# badi.net
KiCad netlist of a schematic drawn in EAGLE
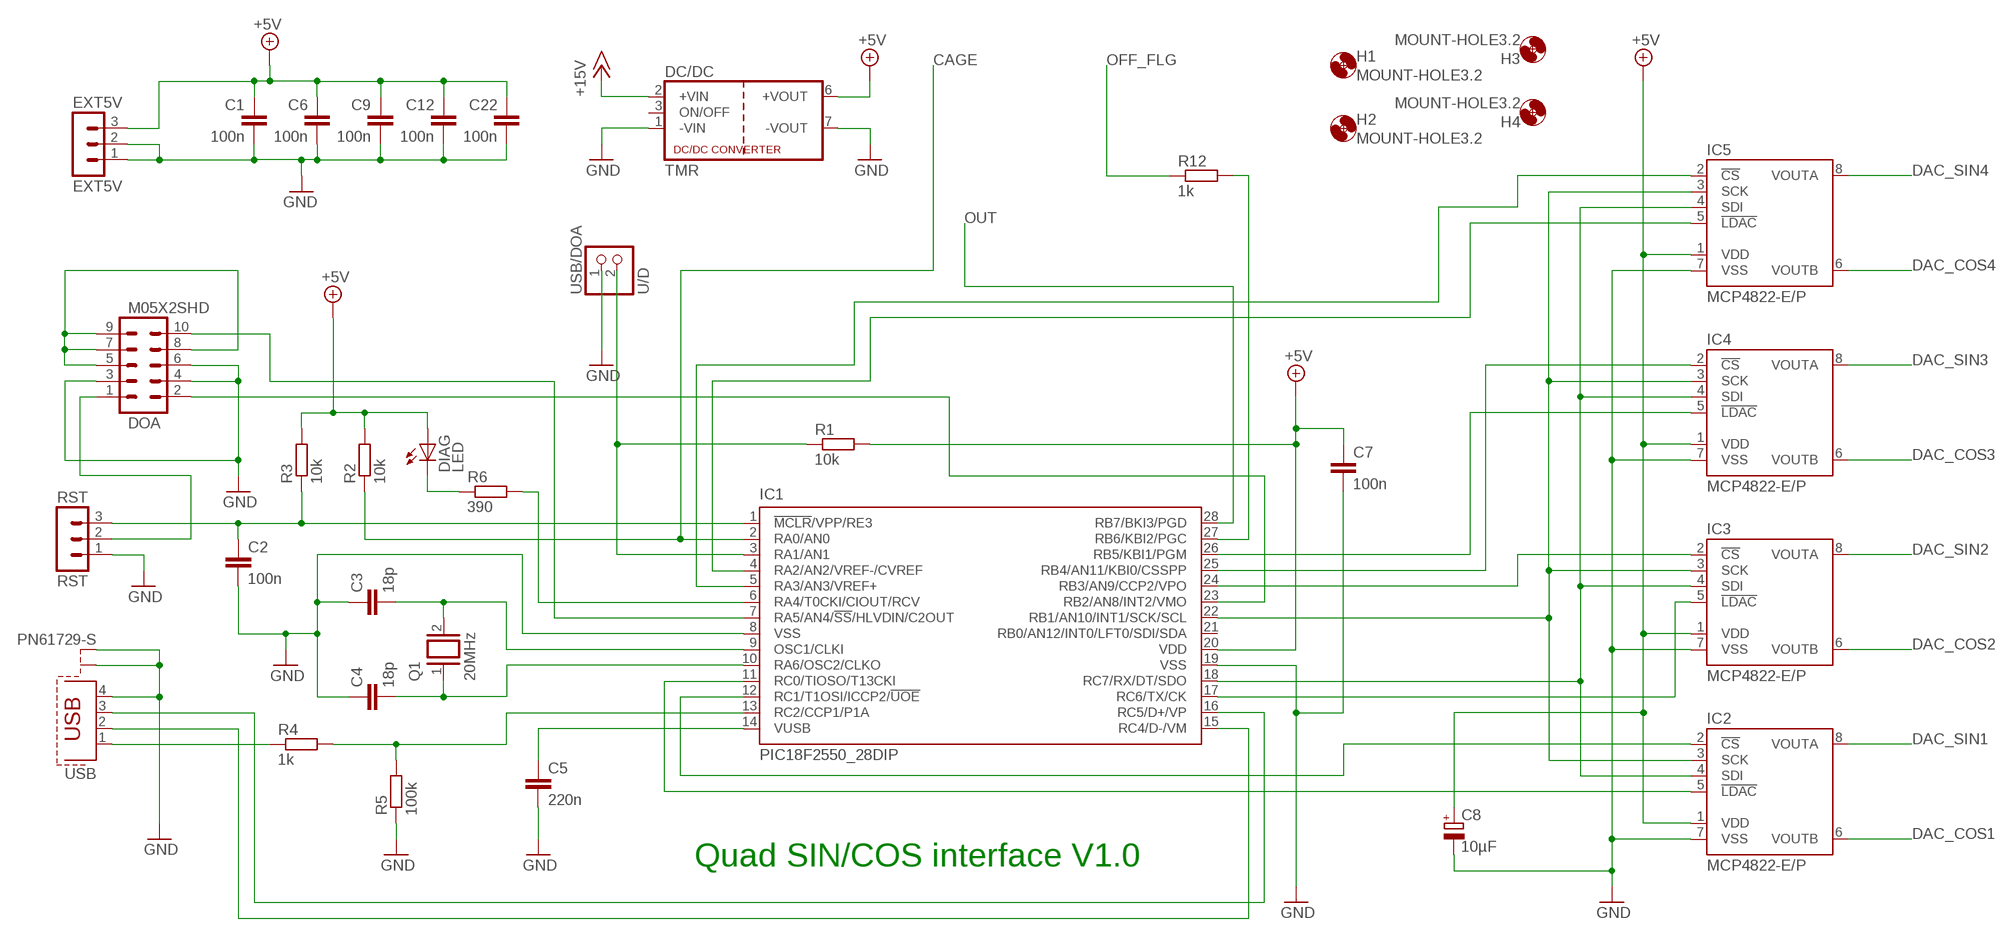
[diagram p0: schematic, sheet 1]
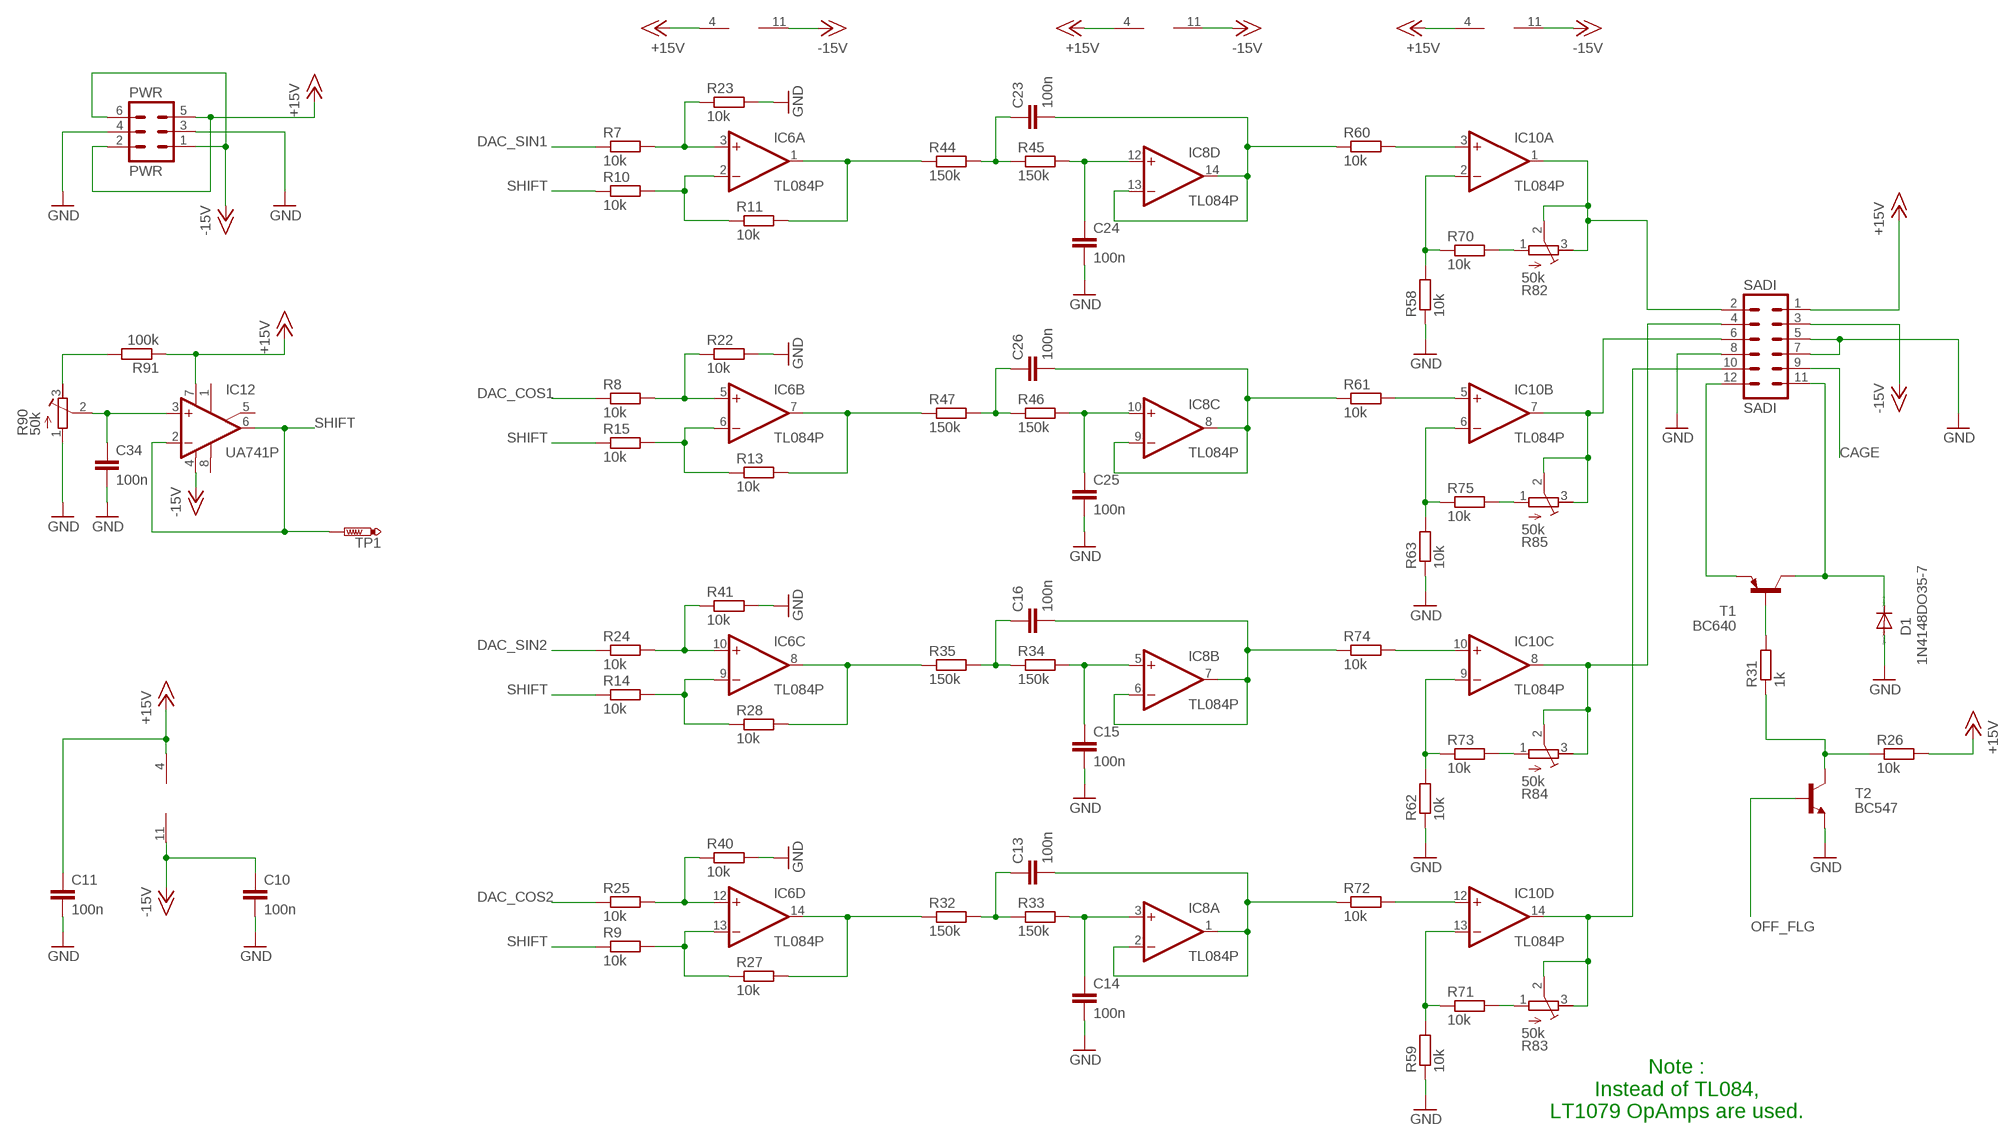
[diagram p1: schematic, sheet 2, part 1 of 2]
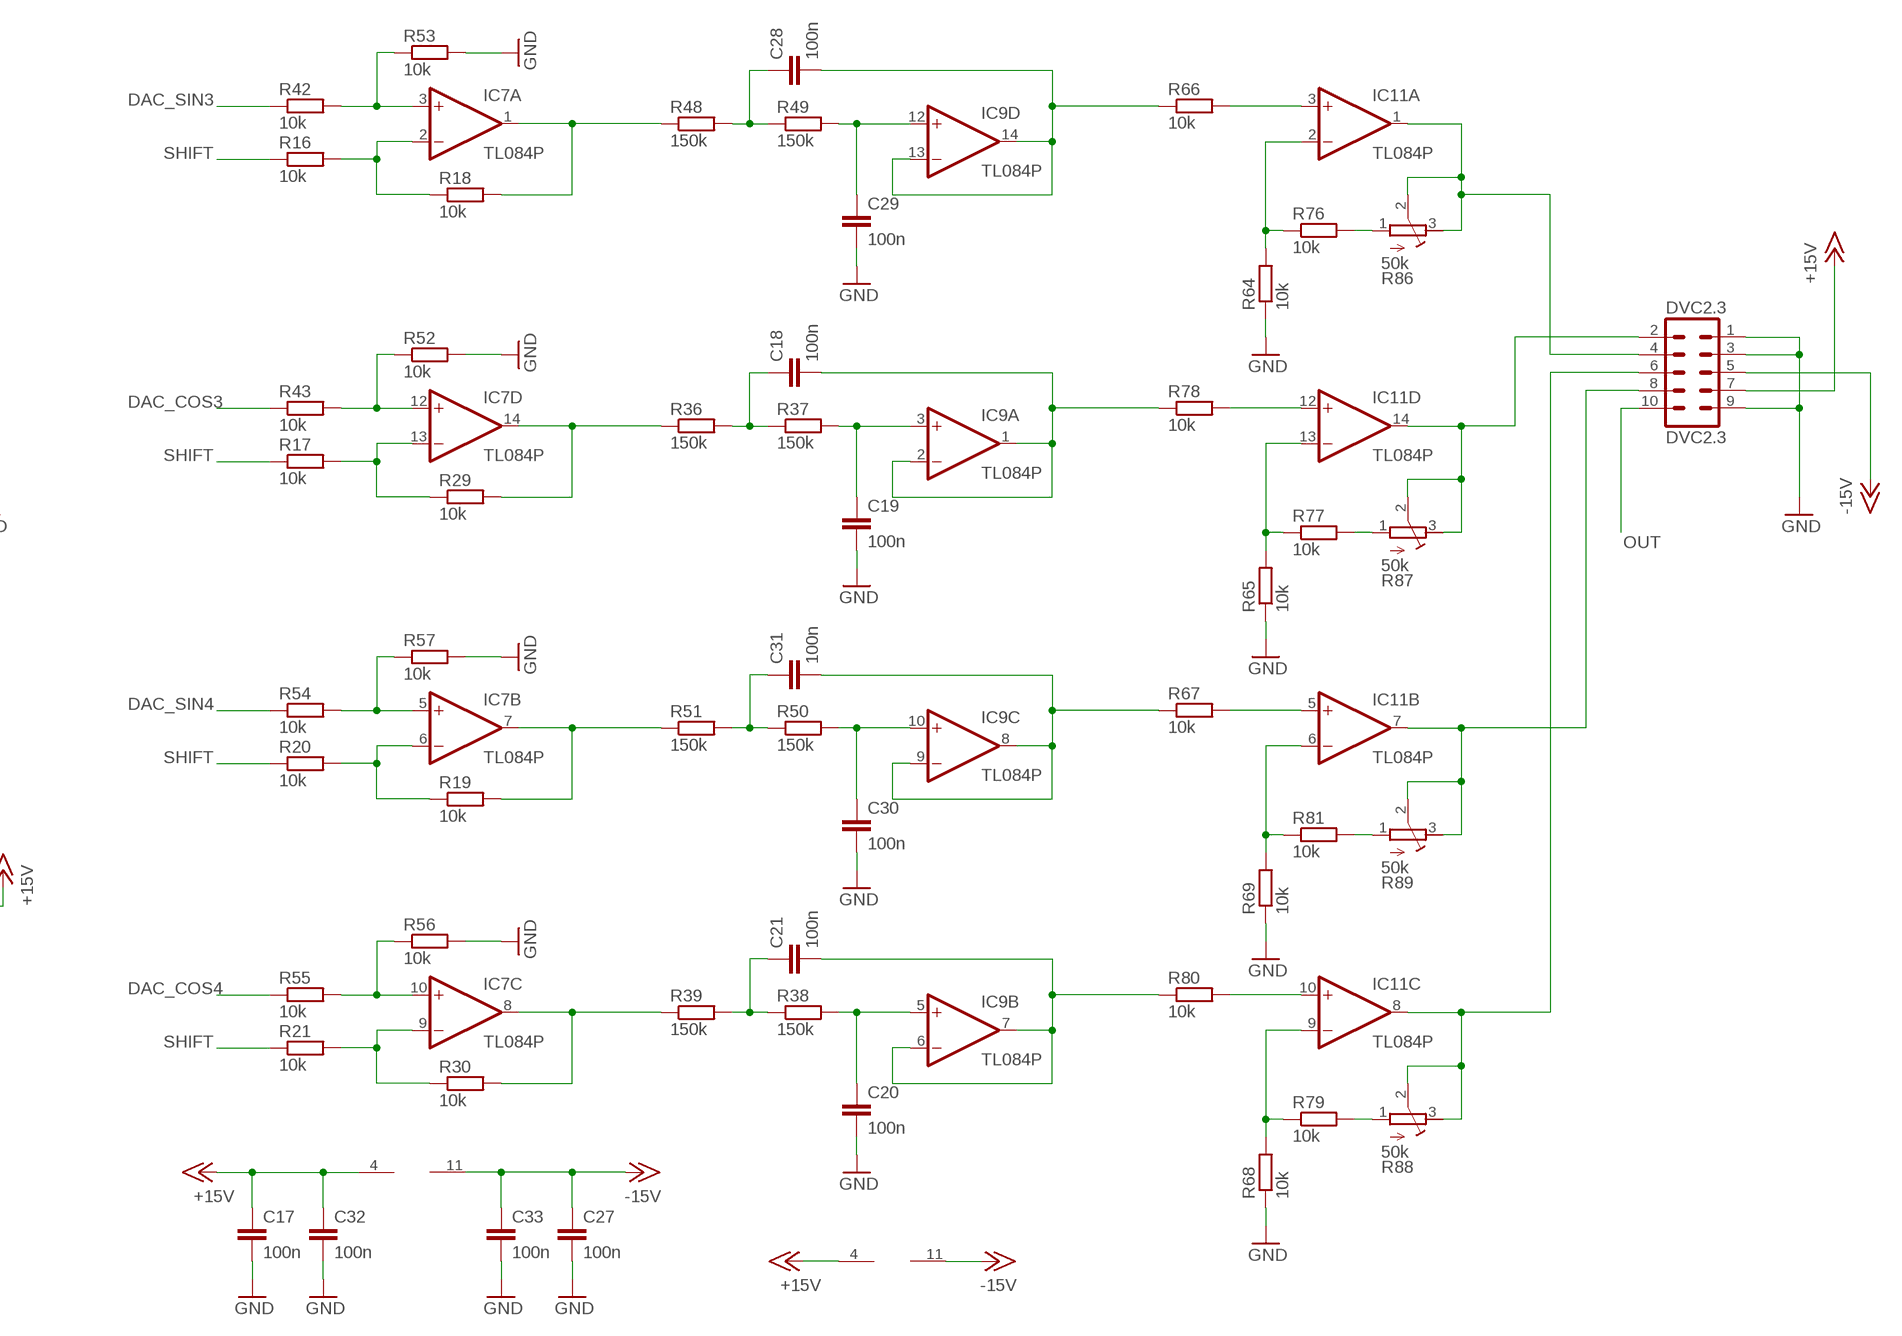
[diagram p2: schematic, sheet 2, part 2 of 2]

(export (version "E")
  (design (tool "Eeschema 10.0.6"))
  (components
    (comp (ref "C1")
      (value "100n")
      (footprint "eagle-import:C025-025X050")
      (libsource (lib "eagle-import") (part "C-EU025-025X050"))
    )
    (comp (ref "C2")
      (value "100n")
      (footprint "eagle-import:C025-025X050")
      (libsource (lib "eagle-import") (part "C-EU025-025X050"))
    )
    (comp (ref "C3")
      (value "18p")
      (footprint "eagle-import:C025-025X050")
      (libsource (lib "eagle-import") (part "C-EU025-025X050"))
    )
    (comp (ref "C4")
      (value "18p")
      (footprint "eagle-import:C025-025X050")
      (libsource (lib "eagle-import") (part "C-EU025-025X050"))
    )
    (comp (ref "C5")
      (value "220n")
      (footprint "eagle-import:C5B3")
      (libsource (lib "eagle-import") (part "C5/3"))
    )
    (comp (ref "C6")
      (value "100n")
      (footprint "eagle-import:C025-025X050")
      (libsource (lib "eagle-import") (part "C-EU025-025X050"))
    )
    (comp (ref "C7")
      (value "100n")
      (footprint "eagle-import:C025-025X050")
      (libsource (lib "eagle-import") (part "C-EU025-025X050"))
    )
    (comp (ref "C8")
      (value "10µF")
      (footprint "eagle-import:E2,5-5")
      (libsource (lib "eagle-import") (part "CPOL-EUE2.5-5"))
    )
    (comp (ref "C9")
      (value "100n")
      (footprint "eagle-import:C025-025X050")
      (libsource (lib "eagle-import") (part "C-EU025-025X050"))
    )
    (comp (ref "C12")
      (value "100n")
      (footprint "eagle-import:C025-025X050")
      (libsource (lib "eagle-import") (part "C-EU025-025X050"))
    )
    (comp (ref "C22")
      (value "100n")
      (footprint "eagle-import:C025-025X050")
      (libsource (lib "eagle-import") (part "C-EU025-025X050"))
    )
    (comp (ref "DC/DC")
      (value "TMR")
      (footprint "eagle-import:TRACO_SIP-8")
      (libsource (lib "eagle-import") (part "TMR"))
    )
    (comp (ref "DIAG")
      (value "LED")
      (footprint "eagle-import:LED3MM")
      (libsource (lib "eagle-import") (part "LED3MM"))
    )
    (comp (ref "DOA")
      (value "M05X2SHD")
      (footprint "eagle-import:2X5-SHROUDED")
      (libsource (lib "eagle-import") (part "M05X2SHD"))
    )
    (comp (ref "EXT5V")
      (value "EXT5V")
      (footprint "eagle-import:MA03-1")
      (libsource (lib "eagle-import") (part "MA03-1"))
    )
    (comp (ref "H1")
      (value "MOUNT-HOLE3.2")
      (footprint "eagle-import:3,2")
      (libsource (lib "eagle-import") (part "MOUNT-HOLE3.2"))
    )
    (comp (ref "H2")
      (value "MOUNT-HOLE3.2")
      (footprint "eagle-import:3,2")
      (libsource (lib "eagle-import") (part "MOUNT-HOLE3.2"))
    )
    (comp (ref "H3")
      (value "MOUNT-HOLE3.2")
      (footprint "eagle-import:3,2")
      (libsource (lib "eagle-import") (part "MOUNT-HOLE3.2"))
    )
    (comp (ref "H4")
      (value "MOUNT-HOLE3.2")
      (footprint "eagle-import:3,2")
      (libsource (lib "eagle-import") (part "MOUNT-HOLE3.2"))
    )
    (comp (ref "IC1")
      (value "PIC18F2550_28DIP")
      (footprint "eagle-import:DIL28-3")
      (fields (field (name "MF") "MICROCHIP") (field (name "MPN") "PIC18F2550-I/SP"))
      (libsource (lib "eagle-import") (part "PIC18F2_28DIP550"))
    )
    (comp (ref "IC2")
      (value "MCP4822-E/P")
      (footprint "eagle-import:DIL08")
      (libsource (lib "eagle-import") (part "MCP4822-E/P"))
    )
    (comp (ref "IC3")
      (value "MCP4822-E/P")
      (footprint "eagle-import:DIL08")
      (libsource (lib "eagle-import") (part "MCP4822-E/P"))
    )
    (comp (ref "IC4")
      (value "MCP4822-E/P")
      (footprint "eagle-import:DIL08")
      (libsource (lib "eagle-import") (part "MCP4822-E/P"))
    )
    (comp (ref "IC5")
      (value "MCP4822-E/P")
      (footprint "eagle-import:DIL08")
      (libsource (lib "eagle-import") (part "MCP4822-E/P"))
    )
    (comp (ref "Q1")
      (value "20MHz")
      (footprint "eagle-import:QS")
      (libsource (lib "eagle-import") (part "XTAL/S"))
    )
    (comp (ref "R1")
      (value "10k")
      (footprint "eagle-import:0204_7")
      (libsource (lib "eagle-import") (part "R-EU_0204/7"))
    )
    (comp (ref "R2")
      (value "10k")
      (footprint "eagle-import:0204_7")
      (libsource (lib "eagle-import") (part "R-EU_0204/7"))
    )
    (comp (ref "R3")
      (value "10k")
      (footprint "eagle-import:0204_7")
      (libsource (lib "eagle-import") (part "R-EU_0204/7"))
    )
    (comp (ref "R4")
      (value "1k")
      (footprint "eagle-import:0204_7")
      (libsource (lib "eagle-import") (part "R-EU_0204/7"))
    )
    (comp (ref "R5")
      (value "100k")
      (footprint "eagle-import:0204_7")
      (libsource (lib "eagle-import") (part "R-EU_0204/7"))
    )
    (comp (ref "R6")
      (value "390")
      (footprint "eagle-import:0204_7")
      (libsource (lib "eagle-import") (part "R-EU_0204/7"))
    )
    (comp (ref "R12")
      (value "1k")
      (footprint "eagle-import:0204_7")
      (libsource (lib "eagle-import") (part "R-EU_0204/7"))
    )
    (comp (ref "RST")
      (value "RST")
      (footprint "eagle-import:MA03-1")
      (libsource (lib "eagle-import") (part "MA03-1"))
    )
    (comp (ref "USB")
      (value "PN61729-S")
      (footprint "eagle-import:PN61729-S")
      (libsource (lib "eagle-import") (part "PN61729-S"))
    )
    (comp (ref "USB/DOA")
      (value "U/D")
      (footprint "eagle-import:1X02")
      (libsource (lib "eagle-import") (part "PINHD-1X2"))
    )
    (comp (ref "C10")
      (value "100n")
      (footprint "eagle-import:C025-025X050")
      (libsource (lib "eagle-import") (part "C-EU025-025X050"))
    )
    (comp (ref "C11")
      (value "100n")
      (footprint "eagle-import:C025-025X050")
      (libsource (lib "eagle-import") (part "C-EU025-025X050"))
    )
    (comp (ref "C13")
      (value "100n")
      (footprint "eagle-import:C025-025X050")
      (libsource (lib "eagle-import") (part "C-EU025-025X050"))
    )
    (comp (ref "C14")
      (value "100n")
      (footprint "eagle-import:C025-025X050")
      (libsource (lib "eagle-import") (part "C-EU025-025X050"))
    )
    (comp (ref "C15")
      (value "100n")
      (footprint "eagle-import:C025-025X050")
      (libsource (lib "eagle-import") (part "C-EU025-025X050"))
    )
    (comp (ref "C16")
      (value "100n")
      (footprint "eagle-import:C025-025X050")
      (libsource (lib "eagle-import") (part "C-EU025-025X050"))
    )
    (comp (ref "C17")
      (value "100n")
      (footprint "eagle-import:C025-025X050")
      (libsource (lib "eagle-import") (part "C-EU025-025X050"))
    )
    (comp (ref "C18")
      (value "100n")
      (footprint "eagle-import:C025-025X050")
      (libsource (lib "eagle-import") (part "C-EU025-025X050"))
    )
    (comp (ref "C19")
      (value "100n")
      (footprint "eagle-import:C025-025X050")
      (libsource (lib "eagle-import") (part "C-EU025-025X050"))
    )
    (comp (ref "C20")
      (value "100n")
      (footprint "eagle-import:C025-025X050")
      (libsource (lib "eagle-import") (part "C-EU025-025X050"))
    )
    (comp (ref "C21")
      (value "100n")
      (footprint "eagle-import:C025-025X050")
      (libsource (lib "eagle-import") (part "C-EU025-025X050"))
    )
    (comp (ref "C23")
      (value "100n")
      (footprint "eagle-import:C025-025X050")
      (libsource (lib "eagle-import") (part "C-EU025-025X050"))
    )
    (comp (ref "C24")
      (value "100n")
      (footprint "eagle-import:C025-025X050")
      (libsource (lib "eagle-import") (part "C-EU025-025X050"))
    )
    (comp (ref "C25")
      (value "100n")
      (footprint "eagle-import:C025-025X050")
      (libsource (lib "eagle-import") (part "C-EU025-025X050"))
    )
    (comp (ref "C26")
      (value "100n")
      (footprint "eagle-import:C025-025X050")
      (libsource (lib "eagle-import") (part "C-EU025-025X050"))
    )
    (comp (ref "C27")
      (value "100n")
      (footprint "eagle-import:C025-025X050")
      (libsource (lib "eagle-import") (part "C-EU025-025X050"))
    )
    (comp (ref "C28")
      (value "100n")
      (footprint "eagle-import:C025-025X050")
      (libsource (lib "eagle-import") (part "C-EU025-025X050"))
    )
    (comp (ref "C29")
      (value "100n")
      (footprint "eagle-import:C025-025X050")
      (libsource (lib "eagle-import") (part "C-EU025-025X050"))
    )
    (comp (ref "C30")
      (value "100n")
      (footprint "eagle-import:C025-025X050")
      (libsource (lib "eagle-import") (part "C-EU025-025X050"))
    )
    (comp (ref "C31")
      (value "100n")
      (footprint "eagle-import:C025-025X050")
      (libsource (lib "eagle-import") (part "C-EU025-025X050"))
    )
    (comp (ref "C32")
      (value "100n")
      (footprint "eagle-import:C025-025X050")
      (libsource (lib "eagle-import") (part "C-EU025-025X050"))
    )
    (comp (ref "C33")
      (value "100n")
      (footprint "eagle-import:C025-025X050")
      (libsource (lib "eagle-import") (part "C-EU025-025X050"))
    )
    (comp (ref "C34")
      (value "100n")
      (footprint "eagle-import:C025-025X050")
      (libsource (lib "eagle-import") (part "C-EU025-025X050"))
    )
    (comp (ref "D1")
      (value "1N4148DO35-7")
      (footprint "eagle-import:DO35-7")
      (libsource (lib "eagle-import") (part "1N4148DO35-7"))
    )
    (comp (ref "DVC2.3")
      (value "DVC2.3")
      (footprint "eagle-import:MA05-2")
      (libsource (lib "eagle-import") (part "MA05-2"))
    )
    (comp (ref "IC6")
      (value "TL084P")
      (footprint "eagle-import:DIL14")
      (libsource (lib "eagle-import") (part "TL084P"))
    )
    (comp (ref "IC7")
      (value "TL084P")
      (footprint "eagle-import:DIL14")
      (libsource (lib "eagle-import") (part "TL084P"))
    )
    (comp (ref "IC8")
      (value "TL084P")
      (footprint "eagle-import:DIL14")
      (libsource (lib "eagle-import") (part "TL084P"))
    )
    (comp (ref "IC9")
      (value "TL084P")
      (footprint "eagle-import:DIL14")
      (libsource (lib "eagle-import") (part "TL084P"))
    )
    (comp (ref "IC10")
      (value "TL084P")
      (footprint "eagle-import:DIL14")
      (libsource (lib "eagle-import") (part "TL084P"))
    )
    (comp (ref "IC11")
      (value "TL084P")
      (footprint "eagle-import:DIL14")
      (libsource (lib "eagle-import") (part "TL084P"))
    )
    (comp (ref "IC12")
      (value "UA741P")
      (footprint "eagle-import:DIL08")
      (libsource (lib "eagle-import") (part "741PUA"))
    )
    (comp (ref "PWR")
      (value "PWR")
      (footprint "eagle-import:MA03-2")
      (libsource (lib "eagle-import") (part "MA03-2"))
    )
    (comp (ref "R7")
      (value "10k")
      (footprint "eagle-import:0204_7")
      (libsource (lib "eagle-import") (part "R-EU_0204/7"))
    )
    (comp (ref "R8")
      (value "10k")
      (footprint "eagle-import:0204_7")
      (libsource (lib "eagle-import") (part "R-EU_0204/7"))
    )
    (comp (ref "R9")
      (value "10k")
      (footprint "eagle-import:0204_7")
      (libsource (lib "eagle-import") (part "R-EU_0204/7"))
    )
    (comp (ref "R10")
      (value "10k")
      (footprint "eagle-import:0204_7")
      (libsource (lib "eagle-import") (part "R-EU_0204/7"))
    )
    (comp (ref "R11")
      (value "10k")
      (footprint "eagle-import:0204_7")
      (libsource (lib "eagle-import") (part "R-EU_0204/7"))
    )
    (comp (ref "R13")
      (value "10k")
      (footprint "eagle-import:0204_7")
      (libsource (lib "eagle-import") (part "R-EU_0204/7"))
    )
    (comp (ref "R14")
      (value "10k")
      (footprint "eagle-import:0204_7")
      (libsource (lib "eagle-import") (part "R-EU_0204/7"))
    )
    (comp (ref "R15")
      (value "10k")
      (footprint "eagle-import:0204_7")
      (libsource (lib "eagle-import") (part "R-EU_0204/7"))
    )
    (comp (ref "R16")
      (value "10k")
      (footprint "eagle-import:0204_7")
      (libsource (lib "eagle-import") (part "R-EU_0204/7"))
    )
    (comp (ref "R17")
      (value "10k")
      (footprint "eagle-import:0204_7")
      (libsource (lib "eagle-import") (part "R-EU_0204/7"))
    )
    (comp (ref "R18")
      (value "10k")
      (footprint "eagle-import:0204_7")
      (libsource (lib "eagle-import") (part "R-EU_0204/7"))
    )
    (comp (ref "R19")
      (value "10k")
      (footprint "eagle-import:0204_7")
      (libsource (lib "eagle-import") (part "R-EU_0204/7"))
    )
    (comp (ref "R20")
      (value "10k")
      (footprint "eagle-import:0204_7")
      (libsource (lib "eagle-import") (part "R-EU_0204/7"))
    )
    (comp (ref "R21")
      (value "10k")
      (footprint "eagle-import:0204_7")
      (libsource (lib "eagle-import") (part "R-EU_0204/7"))
    )
    (comp (ref "R22")
      (value "10k")
      (footprint "eagle-import:0204_7")
      (libsource (lib "eagle-import") (part "R-EU_0204/7"))
    )
    (comp (ref "R23")
      (value "10k")
      (footprint "eagle-import:0204_7")
      (libsource (lib "eagle-import") (part "R-EU_0204/7"))
    )
    (comp (ref "R24")
      (value "10k")
      (footprint "eagle-import:0204_7")
      (libsource (lib "eagle-import") (part "R-EU_0204/7"))
    )
    (comp (ref "R25")
      (value "10k")
      (footprint "eagle-import:0204_7")
      (libsource (lib "eagle-import") (part "R-EU_0204/7"))
    )
    (comp (ref "R26")
      (value "10k")
      (footprint "eagle-import:0204_7")
      (libsource (lib "eagle-import") (part "R-EU_0204/7"))
    )
    (comp (ref "R27")
      (value "10k")
      (footprint "eagle-import:0204_7")
      (libsource (lib "eagle-import") (part "R-EU_0204/7"))
    )
    (comp (ref "R28")
      (value "10k")
      (footprint "eagle-import:0204_7")
      (libsource (lib "eagle-import") (part "R-EU_0204/7"))
    )
    (comp (ref "R29")
      (value "10k")
      (footprint "eagle-import:0204_7")
      (libsource (lib "eagle-import") (part "R-EU_0204/7"))
    )
    (comp (ref "R30")
      (value "10k")
      (footprint "eagle-import:0204_7")
      (libsource (lib "eagle-import") (part "R-EU_0204/7"))
    )
    (comp (ref "R31")
      (value "1k")
      (footprint "eagle-import:0204_7")
      (libsource (lib "eagle-import") (part "R-EU_0204/7"))
    )
    (comp (ref "R32")
      (value "150k")
      (footprint "eagle-import:0204_7")
      (libsource (lib "eagle-import") (part "R-EU_0204/7"))
    )
    (comp (ref "R33")
      (value "150k")
      (footprint "eagle-import:0204_7")
      (libsource (lib "eagle-import") (part "R-EU_0204/7"))
    )
    (comp (ref "R34")
      (value "150k")
      (footprint "eagle-import:0204_7")
      (libsource (lib "eagle-import") (part "R-EU_0204/7"))
    )
    (comp (ref "R35")
      (value "150k")
      (footprint "eagle-import:0204_7")
      (libsource (lib "eagle-import") (part "R-EU_0204/7"))
    )
    (comp (ref "R36")
      (value "150k")
      (footprint "eagle-import:0204_7")
      (libsource (lib "eagle-import") (part "R-EU_0204/7"))
    )
    (comp (ref "R37")
      (value "150k")
      (footprint "eagle-import:0204_7")
      (libsource (lib "eagle-import") (part "R-EU_0204/7"))
    )
    (comp (ref "R38")
      (value "150k")
      (footprint "eagle-import:0204_7")
      (libsource (lib "eagle-import") (part "R-EU_0204/7"))
    )
    (comp (ref "R39")
      (value "150k")
      (footprint "eagle-import:0204_7")
      (libsource (lib "eagle-import") (part "R-EU_0204/7"))
    )
    (comp (ref "R40")
      (value "10k")
      (footprint "eagle-import:0204_7")
      (libsource (lib "eagle-import") (part "R-EU_0204/7"))
    )
    (comp (ref "R41")
      (value "10k")
      (footprint "eagle-import:0204_7")
      (libsource (lib "eagle-import") (part "R-EU_0204/7"))
    )
    (comp (ref "R42")
      (value "10k")
      (footprint "eagle-import:0204_7")
      (libsource (lib "eagle-import") (part "R-EU_0204/7"))
    )
    (comp (ref "R43")
      (value "10k")
      (footprint "eagle-import:0204_7")
      (libsource (lib "eagle-import") (part "R-EU_0204/7"))
    )
    (comp (ref "R44")
      (value "150k")
      (footprint "eagle-import:0204_7")
      (libsource (lib "eagle-import") (part "R-EU_0204/7"))
    )
    (comp (ref "R45")
      (value "150k")
      (footprint "eagle-import:0204_7")
      (libsource (lib "eagle-import") (part "R-EU_0204/7"))
    )
    (comp (ref "R46")
      (value "150k")
      (footprint "eagle-import:0204_7")
      (libsource (lib "eagle-import") (part "R-EU_0204/7"))
    )
    (comp (ref "R47")
      (value "150k")
      (footprint "eagle-import:0204_7")
      (libsource (lib "eagle-import") (part "R-EU_0204/7"))
    )
    (comp (ref "R48")
      (value "150k")
      (footprint "eagle-import:0204_7")
      (libsource (lib "eagle-import") (part "R-EU_0204/7"))
    )
    (comp (ref "R49")
      (value "150k")
      (footprint "eagle-import:0204_7")
      (libsource (lib "eagle-import") (part "R-EU_0204/7"))
    )
    (comp (ref "R50")
      (value "150k")
      (footprint "eagle-import:0204_7")
      (libsource (lib "eagle-import") (part "R-EU_0204/7"))
    )
    (comp (ref "R51")
      (value "150k")
      (footprint "eagle-import:0204_7")
      (libsource (lib "eagle-import") (part "R-EU_0204/7"))
    )
    (comp (ref "R52")
      (value "10k")
      (footprint "eagle-import:0204_7")
      (libsource (lib "eagle-import") (part "R-EU_0204/7"))
    )
    (comp (ref "R53")
      (value "10k")
      (footprint "eagle-import:0204_7")
      (libsource (lib "eagle-import") (part "R-EU_0204/7"))
    )
    (comp (ref "R54")
      (value "10k")
      (footprint "eagle-import:0204_7")
      (libsource (lib "eagle-import") (part "R-EU_0204/7"))
    )
    (comp (ref "R55")
      (value "10k")
      (footprint "eagle-import:0204_7")
      (libsource (lib "eagle-import") (part "R-EU_0204/7"))
    )
    (comp (ref "R56")
      (value "10k")
      (footprint "eagle-import:0204_7")
      (libsource (lib "eagle-import") (part "R-EU_0204/7"))
    )
    (comp (ref "R57")
      (value "10k")
      (footprint "eagle-import:0204_7")
      (libsource (lib "eagle-import") (part "R-EU_0204/7"))
    )
    (comp (ref "R58")
      (value "10k")
      (footprint "eagle-import:0204_7")
      (libsource (lib "eagle-import") (part "R-EU_0204/7"))
    )
    (comp (ref "R59")
      (value "10k")
      (footprint "eagle-import:0204_7")
      (libsource (lib "eagle-import") (part "R-EU_0204/7"))
    )
    (comp (ref "R60")
      (value "10k")
      (footprint "eagle-import:0204_7")
      (libsource (lib "eagle-import") (part "R-EU_0204/7"))
    )
    (comp (ref "R61")
      (value "10k")
      (footprint "eagle-import:0204_7")
      (libsource (lib "eagle-import") (part "R-EU_0204/7"))
    )
    (comp (ref "R62")
      (value "10k")
      (footprint "eagle-import:0204_7")
      (libsource (lib "eagle-import") (part "R-EU_0204/7"))
    )
    (comp (ref "R63")
      (value "10k")
      (footprint "eagle-import:0204_7")
      (libsource (lib "eagle-import") (part "R-EU_0204/7"))
    )
    (comp (ref "R64")
      (value "10k")
      (footprint "eagle-import:0204_7")
      (libsource (lib "eagle-import") (part "R-EU_0204/7"))
    )
    (comp (ref "R65")
      (value "10k")
      (footprint "eagle-import:0204_7")
      (libsource (lib "eagle-import") (part "R-EU_0204/7"))
    )
    (comp (ref "R66")
      (value "10k")
      (footprint "eagle-import:0204_7")
      (libsource (lib "eagle-import") (part "R-EU_0204/7"))
    )
    (comp (ref "R67")
      (value "10k")
      (footprint "eagle-import:0204_7")
      (libsource (lib "eagle-import") (part "R-EU_0204/7"))
    )
    (comp (ref "R68")
      (value "10k")
      (footprint "eagle-import:0204_7")
      (libsource (lib "eagle-import") (part "R-EU_0204/7"))
    )
    (comp (ref "R69")
      (value "10k")
      (footprint "eagle-import:0204_7")
      (libsource (lib "eagle-import") (part "R-EU_0204/7"))
    )
    (comp (ref "R70")
      (value "10k")
      (footprint "eagle-import:0204_7")
      (libsource (lib "eagle-import") (part "R-EU_0204/7"))
    )
    (comp (ref "R71")
      (value "10k")
      (footprint "eagle-import:0204_7")
      (libsource (lib "eagle-import") (part "R-EU_0204/7"))
    )
    (comp (ref "R72")
      (value "10k")
      (footprint "eagle-import:0204_7")
      (libsource (lib "eagle-import") (part "R-EU_0204/7"))
    )
    (comp (ref "R73")
      (value "10k")
      (footprint "eagle-import:0204_7")
      (libsource (lib "eagle-import") (part "R-EU_0204/7"))
    )
    (comp (ref "R74")
      (value "10k")
      (footprint "eagle-import:0204_7")
      (libsource (lib "eagle-import") (part "R-EU_0204/7"))
    )
    (comp (ref "R75")
      (value "10k")
      (footprint "eagle-import:0204_7")
      (libsource (lib "eagle-import") (part "R-EU_0204/7"))
    )
    (comp (ref "R76")
      (value "10k")
      (footprint "eagle-import:0204_7")
      (libsource (lib "eagle-import") (part "R-EU_0204/7"))
    )
    (comp (ref "R77")
      (value "10k")
      (footprint "eagle-import:0204_7")
      (libsource (lib "eagle-import") (part "R-EU_0204/7"))
    )
    (comp (ref "R78")
      (value "10k")
      (footprint "eagle-import:0204_7")
      (libsource (lib "eagle-import") (part "R-EU_0204/7"))
    )
    (comp (ref "R79")
      (value "10k")
      (footprint "eagle-import:0204_7")
      (libsource (lib "eagle-import") (part "R-EU_0204/7"))
    )
    (comp (ref "R80")
      (value "10k")
      (footprint "eagle-import:0204_7")
      (libsource (lib "eagle-import") (part "R-EU_0204/7"))
    )
    (comp (ref "R81")
      (value "10k")
      (footprint "eagle-import:0204_7")
      (libsource (lib "eagle-import") (part "R-EU_0204/7"))
    )
    (comp (ref "R82")
      (value "50k")
      (footprint "eagle-import:RTRIM64Z")
      (libsource (lib "eagle-import") (part "R-TRIMM64Z"))
    )
    (comp (ref "R83")
      (value "50k")
      (footprint "eagle-import:RTRIM64Z")
      (libsource (lib "eagle-import") (part "R-TRIMM64Z"))
    )
    (comp (ref "R84")
      (value "50k")
      (footprint "eagle-import:RTRIM64Z")
      (libsource (lib "eagle-import") (part "R-TRIMM64Z"))
    )
    (comp (ref "R85")
      (value "50k")
      (footprint "eagle-import:RTRIM64Z")
      (libsource (lib "eagle-import") (part "R-TRIMM64Z"))
    )
    (comp (ref "R86")
      (value "50k")
      (footprint "eagle-import:RTRIM64Z")
      (libsource (lib "eagle-import") (part "R-TRIMM64Z"))
    )
    (comp (ref "R87")
      (value "50k")
      (footprint "eagle-import:RTRIM64Z")
      (libsource (lib "eagle-import") (part "R-TRIMM64Z"))
    )
    (comp (ref "R88")
      (value "50k")
      (footprint "eagle-import:RTRIM64Z")
      (libsource (lib "eagle-import") (part "R-TRIMM64Z"))
    )
    (comp (ref "R89")
      (value "50k")
      (footprint "eagle-import:RTRIM64Z")
      (libsource (lib "eagle-import") (part "R-TRIMM64Z"))
    )
    (comp (ref "R90")
      (value "50k")
      (footprint "eagle-import:RTRIM64Z")
      (libsource (lib "eagle-import") (part "R-TRIMM64Z"))
    )
    (comp (ref "R91")
      (value "100k")
      (footprint "eagle-import:0204_7")
      (libsource (lib "eagle-import") (part "R-EU_0204/7"))
    )
    (comp (ref "SADI")
      (value "SADI")
      (footprint "eagle-import:MA06-2")
      (libsource (lib "eagle-import") (part "MA06-2"))
    )
    (comp (ref "T1")
      (value "BC640")
      (footprint "eagle-import:TO92-BCE")
      (libsource (lib "eagle-import") (part "BC640"))
    )
    (comp (ref "T2")
      (value "BC547")
      (footprint "eagle-import:TO92-CBE")
      (libsource (lib "eagle-import") (part "-NPN-TO92-CBEBC547"))
    )
    (comp (ref "TP1")
      (value "PTR1B1,27")
      (footprint "eagle-import:B1,27")
      (libsource (lib "eagle-import") (part "PTR1B1,27"))
    )
  )
  (nets
    (net (code "1") (name "+5V") (class "Default")
      (node (ref "C1") (pin "1") (pinfunction "1_1") (pintype "passive"))
      (node (ref "C12") (pin "1") (pinfunction "1_1") (pintype "passive"))
      (node (ref "C22") (pin "1") (pinfunction "1_1") (pintype "passive"))
      (node (ref "C6") (pin "1") (pinfunction "1_1") (pintype "passive"))
      (node (ref "C7") (pin "1") (pinfunction "1_1") (pintype "passive"))
      (node (ref "C8") (pin "+") (pinfunction "+_+") (pintype "passive"))
      (node (ref "C9") (pin "1") (pinfunction "1_1") (pintype "passive"))
      (node (ref "DC/DC") (pin "6") (pinfunction "+VOUT_6") (pintype "passive"))
      (node (ref "DIAG") (pin "A") (pinfunction "A_A") (pintype "passive"))
      (node (ref "EXT5V") (pin "3") (pinfunction "3_3") (pintype "passive"))
      (node (ref "IC1") (pin "20") (pinfunction "VDD_20") (pintype "power_in"))
      (node (ref "IC2") (pin "1") (pinfunction "VDD_1") (pintype "power_in"))
      (node (ref "IC3") (pin "1") (pinfunction "VDD_1") (pintype "power_in"))
      (node (ref "IC4") (pin "1") (pinfunction "VDD_1") (pintype "power_in"))
      (node (ref "IC5") (pin "1") (pinfunction "VDD_1") (pintype "power_in"))
      (node (ref "R1") (pin "2") (pinfunction "2_2") (pintype "passive"))
      (node (ref "R2") (pin "2") (pinfunction "2_2") (pintype "passive"))
      (node (ref "R3") (pin "2") (pinfunction "2_2") (pintype "passive"))
    )
    (net (code "2") (name "+15V") (class "Default")
      (node (ref "C11") (pin "1") (pinfunction "1_1") (pintype "passive"))
      (node (ref "C17") (pin "1") (pinfunction "1_1") (pintype "passive"))
      (node (ref "C32") (pin "1") (pinfunction "1_1") (pintype "passive"))
      (node (ref "DC/DC") (pin "2") (pinfunction "+VIN_2") (pintype "passive"))
      (node (ref "DVC2.3") (pin "7") (pinfunction "7_7") (pintype "passive"))
      (node (ref "IC10") (pin "4") (pinfunction "V+_4") (pintype "power_in"))
      (node (ref "IC11") (pin "4") (pinfunction "V+_4") (pintype "power_in"))
      (node (ref "IC12") (pin "7") (pinfunction "V+_7") (pintype "power_in"))
      (node (ref "IC6") (pin "4") (pinfunction "V+_4") (pintype "power_in"))
      (node (ref "IC7") (pin "4") (pinfunction "V+_4") (pintype "power_in"))
      (node (ref "IC8") (pin "4") (pinfunction "V+_4") (pintype "power_in"))
      (node (ref "IC9") (pin "4") (pinfunction "V+_4") (pintype "power_in"))
      (node (ref "PWR") (pin "2") (pinfunction "2_2") (pintype "passive"))
      (node (ref "PWR") (pin "5") (pinfunction "5_5") (pintype "passive"))
      (node (ref "R26") (pin "2") (pinfunction "2_2") (pintype "passive"))
      (node (ref "R91") (pin "1") (pinfunction "1_1") (pintype "passive"))
      (node (ref "SADI") (pin "1") (pinfunction "1_1") (pintype "passive"))
    )
    (net (code "3") (name "-15V") (class "Default")
      (node (ref "C10") (pin "1") (pinfunction "1_1") (pintype "passive"))
      (node (ref "C27") (pin "1") (pinfunction "1_1") (pintype "passive"))
      (node (ref "C33") (pin "1") (pinfunction "1_1") (pintype "passive"))
      (node (ref "DVC2.3") (pin "5") (pinfunction "5_5") (pintype "passive"))
      (node (ref "IC10") (pin "11") (pinfunction "V-_11") (pintype "power_in"))
      (node (ref "IC11") (pin "11") (pinfunction "V-_11") (pintype "power_in"))
      (node (ref "IC12") (pin "4") (pinfunction "V-_4") (pintype "power_in"))
      (node (ref "IC6") (pin "11") (pinfunction "V-_11") (pintype "power_in"))
      (node (ref "IC7") (pin "11") (pinfunction "V-_11") (pintype "power_in"))
      (node (ref "IC8") (pin "11") (pinfunction "V-_11") (pintype "power_in"))
      (node (ref "IC9") (pin "11") (pinfunction "V-_11") (pintype "power_in"))
      (node (ref "PWR") (pin "1") (pinfunction "1_1") (pintype "passive"))
      (node (ref "PWR") (pin "6") (pinfunction "6_6") (pintype "passive"))
      (node (ref "SADI") (pin "3") (pinfunction "3_3") (pintype "passive"))
    )
    (net (code "4") (name "CAGE") (class "Default")
      (node (ref "IC1") (pin "2") (pinfunction "RA0/AN0_2") (pintype "bidirectional"))
      (node (ref "R2") (pin "1") (pinfunction "1_1") (pintype "passive"))
      (node (ref "SADI") (pin "9") (pinfunction "9_9") (pintype "passive"))
    )
    (net (code "5") (name "DAC_COS1") (class "Default")
      (node (ref "IC2") (pin "6") (pinfunction "VOUTB_6") (pintype "output"))
      (node (ref "R8") (pin "1") (pinfunction "1_1") (pintype "passive"))
    )
    (net (code "6") (name "DAC_COS2") (class "Default")
      (node (ref "IC3") (pin "6") (pinfunction "VOUTB_6") (pintype "output"))
      (node (ref "R25") (pin "1") (pinfunction "1_1") (pintype "passive"))
    )
    (net (code "7") (name "DAC_COS3") (class "Default")
      (node (ref "IC4") (pin "6") (pinfunction "VOUTB_6") (pintype "output"))
      (node (ref "R43") (pin "1") (pinfunction "1_1") (pintype "passive"))
    )
    (net (code "8") (name "DAC_COS4") (class "Default")
      (node (ref "IC5") (pin "6") (pinfunction "VOUTB_6") (pintype "output"))
      (node (ref "R55") (pin "1") (pinfunction "1_1") (pintype "passive"))
    )
    (net (code "9") (name "DAC_SIN1") (class "Default")
      (node (ref "IC2") (pin "8") (pinfunction "VOUTA_8") (pintype "output"))
      (node (ref "R7") (pin "1") (pinfunction "1_1") (pintype "passive"))
    )
    (net (code "10") (name "DAC_SIN2") (class "Default")
      (node (ref "IC3") (pin "8") (pinfunction "VOUTA_8") (pintype "output"))
      (node (ref "R24") (pin "1") (pinfunction "1_1") (pintype "passive"))
    )
    (net (code "11") (name "DAC_SIN3") (class "Default")
      (node (ref "IC4") (pin "8") (pinfunction "VOUTA_8") (pintype "output"))
      (node (ref "R42") (pin "1") (pinfunction "1_1") (pintype "passive"))
    )
    (net (code "12") (name "DAC_SIN4") (class "Default")
      (node (ref "IC5") (pin "8") (pinfunction "VOUTA_8") (pintype "output"))
      (node (ref "R54") (pin "1") (pinfunction "1_1") (pintype "passive"))
    )
    (net (code "13") (name "GND") (class "Default")
      (node (ref "C1") (pin "2") (pinfunction "2_2") (pintype "passive"))
      (node (ref "C10") (pin "2") (pinfunction "2_2") (pintype "passive"))
      (node (ref "C11") (pin "2") (pinfunction "2_2") (pintype "passive"))
      (node (ref "C12") (pin "2") (pinfunction "2_2") (pintype "passive"))
      (node (ref "C14") (pin "2") (pinfunction "2_2") (pintype "passive"))
      (node (ref "C15") (pin "2") (pinfunction "2_2") (pintype "passive"))
      (node (ref "C17") (pin "2") (pinfunction "2_2") (pintype "passive"))
      (node (ref "C19") (pin "2") (pinfunction "2_2") (pintype "passive"))
      (node (ref "C2") (pin "2") (pinfunction "2_2") (pintype "passive"))
      (node (ref "C20") (pin "2") (pinfunction "2_2") (pintype "passive"))
      (node (ref "C22") (pin "2") (pinfunction "2_2") (pintype "passive"))
      (node (ref "C24") (pin "2") (pinfunction "2_2") (pintype "passive"))
      (node (ref "C25") (pin "2") (pinfunction "2_2") (pintype "passive"))
      (node (ref "C27") (pin "2") (pinfunction "2_2") (pintype "passive"))
      (node (ref "C29") (pin "2") (pinfunction "2_2") (pintype "passive"))
      (node (ref "C3") (pin "1") (pinfunction "1_1") (pintype "passive"))
      (node (ref "C30") (pin "2") (pinfunction "2_2") (pintype "passive"))
      (node (ref "C32") (pin "2") (pinfunction "2_2") (pintype "passive"))
      (node (ref "C33") (pin "2") (pinfunction "2_2") (pintype "passive"))
      (node (ref "C34") (pin "2") (pinfunction "2_2") (pintype "passive"))
      (node (ref "C4") (pin "1") (pinfunction "1_1") (pintype "passive"))
      (node (ref "C5") (pin "2") (pinfunction "2_2") (pintype "passive"))
      (node (ref "C6") (pin "2") (pinfunction "2_2") (pintype "passive"))
      (node (ref "C7") (pin "2") (pinfunction "2_2") (pintype "passive"))
      (node (ref "C8") (pin "-") (pinfunction "-_-") (pintype "passive"))
      (node (ref "C9") (pin "2") (pinfunction "2_2") (pintype "passive"))
      (node (ref "D1") (pin "A") (pinfunction "A_A") (pintype "passive"))
      (node (ref "DC/DC") (pin "1") (pinfunction "-VIN_1") (pintype "passive"))
      (node (ref "DC/DC") (pin "7") (pinfunction "-VOUT_7") (pintype "passive"))
      (node (ref "DOA") (pin "3") (pinfunction "3_3") (pintype "passive"))
      (node (ref "DOA") (pin "4") (pinfunction "4_4") (pintype "passive"))
      (node (ref "DOA") (pin "6") (pinfunction "6_6") (pintype "passive"))
      (node (ref "DVC2.3") (pin "1") (pinfunction "1_1") (pintype "passive"))
      (node (ref "DVC2.3") (pin "3") (pinfunction "3_3") (pintype "passive"))
      (node (ref "DVC2.3") (pin "9") (pinfunction "9_9") (pintype "passive"))
      (node (ref "EXT5V") (pin "1") (pinfunction "1_1") (pintype "passive"))
      (node (ref "EXT5V") (pin "2") (pinfunction "2_2") (pintype "passive"))
      (node (ref "IC1") (pin "19") (pinfunction "VSS_19") (pintype "power_in"))
      (node (ref "IC1") (pin "8") (pinfunction "VSS_8") (pintype "power_in"))
      (node (ref "IC2") (pin "7") (pinfunction "VSS_7") (pintype "power_in"))
      (node (ref "IC3") (pin "7") (pinfunction "VSS_7") (pintype "power_in"))
      (node (ref "IC4") (pin "7") (pinfunction "VSS_7") (pintype "power_in"))
      (node (ref "IC5") (pin "7") (pinfunction "VSS_7") (pintype "power_in"))
      (node (ref "PWR") (pin "3") (pinfunction "3_3") (pintype "passive"))
      (node (ref "PWR") (pin "4") (pinfunction "4_4") (pintype "passive"))
      (node (ref "R22") (pin "2") (pinfunction "2_2") (pintype "passive"))
      (node (ref "R23") (pin "2") (pinfunction "2_2") (pintype "passive"))
      (node (ref "R40") (pin "2") (pinfunction "2_2") (pintype "passive"))
      (node (ref "R41") (pin "2") (pinfunction "2_2") (pintype "passive"))
      (node (ref "R5") (pin "1") (pinfunction "1_1") (pintype "passive"))
      (node (ref "R52") (pin "2") (pinfunction "2_2") (pintype "passive"))
      (node (ref "R53") (pin "2") (pinfunction "2_2") (pintype "passive"))
      (node (ref "R56") (pin "2") (pinfunction "2_2") (pintype "passive"))
      (node (ref "R57") (pin "2") (pinfunction "2_2") (pintype "passive"))
      (node (ref "R58") (pin "1") (pinfunction "1_1") (pintype "passive"))
      (node (ref "R59") (pin "1") (pinfunction "1_1") (pintype "passive"))
      (node (ref "R62") (pin "1") (pinfunction "1_1") (pintype "passive"))
      (node (ref "R63") (pin "1") (pinfunction "1_1") (pintype "passive"))
      (node (ref "R64") (pin "1") (pinfunction "1_1") (pintype "passive"))
      (node (ref "R65") (pin "1") (pinfunction "1_1") (pintype "passive"))
      (node (ref "R68") (pin "1") (pinfunction "1_1") (pintype "passive"))
      (node (ref "R69") (pin "1") (pinfunction "1_1") (pintype "passive"))
      (node (ref "R90") (pin "1") (pinfunction "A_1") (pintype "passive"))
      (node (ref "RST") (pin "1") (pinfunction "1_1") (pintype "passive"))
      (node (ref "SADI") (pin "5") (pinfunction "5_5") (pintype "passive"))
      (node (ref "SADI") (pin "7") (pinfunction "7_7") (pintype "passive"))
      (node (ref "SADI") (pin "8") (pinfunction "8_8") (pintype "passive"))
      (node (ref "T2") (pin "E") (pinfunction "E_E") (pintype "passive"))
      (node (ref "USB") (pin "4") (pinfunction "4_4") (pintype "passive"))
      (node (ref "USB") (pin "S1") (pinfunction "S1_S1") (pintype "passive"))
      (node (ref "USB") (pin "S2") (pinfunction "S2_S2") (pintype "passive"))
      (node (ref "USB/DOA") (pin "1") (pinfunction "1_1") (pintype "passive"))
    )
    (net (code "14") (name "Net-(C13-Pad1)") (class "Default")
      (node (ref "C13") (pin "1") (pinfunction "1_1") (pintype "passive"))
      (node (ref "R32") (pin "2") (pinfunction "2_2") (pintype "passive"))
      (node (ref "R33") (pin "1") (pinfunction "1_1") (pintype "passive"))
    )
    (net (code "15") (name "Net-(C16-Pad1)") (class "Default")
      (node (ref "C16") (pin "1") (pinfunction "1_1") (pintype "passive"))
      (node (ref "R34") (pin "1") (pinfunction "1_1") (pintype "passive"))
      (node (ref "R35") (pin "2") (pinfunction "2_2") (pintype "passive"))
    )
    (net (code "16") (name "Net-(C18-Pad1)") (class "Default")
      (node (ref "C18") (pin "1") (pinfunction "1_1") (pintype "passive"))
      (node (ref "R36") (pin "2") (pinfunction "2_2") (pintype "passive"))
      (node (ref "R37") (pin "1") (pinfunction "1_1") (pintype "passive"))
    )
    (net (code "17") (name "Net-(C21-Pad1)") (class "Default")
      (node (ref "C21") (pin "1") (pinfunction "1_1") (pintype "passive"))
      (node (ref "R38") (pin "1") (pinfunction "1_1") (pintype "passive"))
      (node (ref "R39") (pin "2") (pinfunction "2_2") (pintype "passive"))
    )
    (net (code "18") (name "Net-(C23-Pad1)") (class "Default")
      (node (ref "C23") (pin "1") (pinfunction "1_1") (pintype "passive"))
      (node (ref "R44") (pin "2") (pinfunction "2_2") (pintype "passive"))
      (node (ref "R45") (pin "1") (pinfunction "1_1") (pintype "passive"))
    )
    (net (code "19") (name "Net-(C26-Pad1)") (class "Default")
      (node (ref "C26") (pin "1") (pinfunction "1_1") (pintype "passive"))
      (node (ref "R46") (pin "1") (pinfunction "1_1") (pintype "passive"))
      (node (ref "R47") (pin "2") (pinfunction "2_2") (pintype "passive"))
    )
    (net (code "20") (name "Net-(C28-Pad1)") (class "Default")
      (node (ref "C28") (pin "1") (pinfunction "1_1") (pintype "passive"))
      (node (ref "R48") (pin "2") (pinfunction "2_2") (pintype "passive"))
      (node (ref "R49") (pin "1") (pinfunction "1_1") (pintype "passive"))
    )
    (net (code "21") (name "Net-(C31-Pad1)") (class "Default")
      (node (ref "C31") (pin "1") (pinfunction "1_1") (pintype "passive"))
      (node (ref "R50") (pin "1") (pinfunction "1_1") (pintype "passive"))
      (node (ref "R51") (pin "2") (pinfunction "2_2") (pintype "passive"))
    )
    (net (code "22") (name "Net-(D1-PadC)") (class "Default")
      (node (ref "D1") (pin "C") (pinfunction "C_C") (pintype "passive"))
      (node (ref "SADI") (pin "11") (pinfunction "11_11") (pintype "passive"))
      (node (ref "T1") (pin "C") (pinfunction "C_C") (pintype "passive"))
    )
    (net (code "23") (name "Net-(DIAG-C)") (class "Default")
      (node (ref "DIAG") (pin "K") (pinfunction "C_K") (pintype "passive"))
      (node (ref "R6") (pin "1") (pinfunction "1_1") (pintype "passive"))
    )
    (net (code "24") (name "Net-(DOA-Pad1)") (class "Default")
      (node (ref "DOA") (pin "1") (pinfunction "1_1") (pintype "passive"))
      (node (ref "RST") (pin "2") (pinfunction "2_2") (pintype "passive"))
    )
    (net (code "25") (name "Net-(DOA-Pad5)") (class "Default")
      (node (ref "DOA") (pin "5") (pinfunction "5_5") (pintype "passive"))
      (node (ref "DOA") (pin "7") (pinfunction "7_7") (pintype "passive"))
      (node (ref "DOA") (pin "8") (pinfunction "8_8") (pintype "passive"))
      (node (ref "DOA") (pin "9") (pinfunction "9_9") (pintype "passive"))
    )
    (net (code "26") (name "Net-(IC1-OSC1{slash}CLKI)") (class "Default")
      (node (ref "C3") (pin "2") (pinfunction "2_2") (pintype "passive"))
      (node (ref "IC1") (pin "9") (pinfunction "OSC1/CLKI_9") (pintype "input"))
      (node (ref "Q1") (pin "2") (pinfunction "2_2") (pintype "passive"))
    )
    (net (code "27") (name "Net-(IC1-RA1{slash}AN1)") (class "Default")
      (node (ref "IC1") (pin "3") (pinfunction "RA1/AN1_3") (pintype "bidirectional"))
      (node (ref "R1") (pin "1") (pinfunction "1_1") (pintype "passive"))
      (node (ref "USB/DOA") (pin "2") (pinfunction "2_2") (pintype "passive"))
    )
    (net (code "28") (name "Net-(IC1-RA2{slash}AN2{slash}VREF-{slash}CVREF)") (class "Default")
      (node (ref "IC1") (pin "4") (pinfunction "RA2/AN2/VREF-/CVREF_4") (pintype "bidirectional"))
      (node (ref "IC5") (pin "5") (pinfunction "~{LDAC}_5") (pintype "input"))
    )
    (net (code "29") (name "Net-(IC1-RA3{slash}AN3{slash}VREF+)") (class "Default")
      (node (ref "IC1") (pin "5") (pinfunction "RA3/AN3/VREF+_5") (pintype "bidirectional"))
      (node (ref "IC5") (pin "2") (pinfunction "~{CS}_2") (pintype "input"))
    )
    (net (code "30") (name "Net-(IC1-RA4{slash}T0CKI{slash}CIOUT{slash}RCV)") (class "Default")
      (node (ref "IC1") (pin "6") (pinfunction "RA4/T0CKI/CIOUT/RCV_6") (pintype "bidirectional"))
      (node (ref "R6") (pin "2") (pinfunction "2_2") (pintype "passive"))
    )
    (net (code "31") (name "Net-(IC1-RA5{slash}AN4{slash}~{SS}{slash}HLVDIN{slash}C2OUT)") (class "Default")
      (node (ref "DOA") (pin "10") (pinfunction "10_10") (pintype "passive"))
      (node (ref "IC1") (pin "7") (pinfunction "RA5/AN4/~{SS}/HLVDIN/C2OUT_7") (pintype "bidirectional"))
    )
    (net (code "32") (name "Net-(IC1-RA6{slash}OSC2{slash}CLKO)") (class "Default")
      (node (ref "C4") (pin "2") (pinfunction "2_2") (pintype "passive"))
      (node (ref "IC1") (pin "10") (pinfunction "RA6/OSC2/CLKO_10") (pintype "output"))
      (node (ref "Q1") (pin "1") (pinfunction "1_1") (pintype "passive"))
    )
    (net (code "33") (name "Net-(IC1-RB1{slash}AN10{slash}INT1{slash}SCK{slash}SCL)") (class "Default")
      (node (ref "IC1") (pin "22") (pinfunction "RB1/AN10/INT1/SCK/SCL_22") (pintype "bidirectional"))
      (node (ref "IC2") (pin "3") (pinfunction "SCK_3") (pintype "input"))
      (node (ref "IC3") (pin "3") (pinfunction "SCK_3") (pintype "input"))
      (node (ref "IC4") (pin "3") (pinfunction "SCK_3") (pintype "input"))
      (node (ref "IC5") (pin "3") (pinfunction "SCK_3") (pintype "input"))
    )
    (net (code "34") (name "Net-(IC1-RB2{slash}AN8{slash}INT2{slash}VMO)") (class "Default")
      (node (ref "DOA") (pin "2") (pinfunction "2_2") (pintype "passive"))
      (node (ref "IC1") (pin "23") (pinfunction "RB2/AN8/INT2/VMO_23") (pintype "bidirectional"))
    )
    (net (code "35") (name "Net-(IC1-RB3{slash}AN9{slash}CCP2{slash}VPO)") (class "Default")
      (node (ref "IC1") (pin "24") (pinfunction "RB3/AN9/CCP2/VPO_24") (pintype "bidirectional"))
      (node (ref "IC3") (pin "2") (pinfunction "~{CS}_2") (pintype "input"))
    )
    (net (code "36") (name "Net-(IC1-RB4{slash}AN11{slash}KBI0{slash}CSSPP)") (class "Default")
      (node (ref "IC1") (pin "25") (pinfunction "RB4/AN11/KBI0/CSSPP_25") (pintype "bidirectional"))
      (node (ref "IC4") (pin "2") (pinfunction "~{CS}_2") (pintype "input"))
    )
    (net (code "37") (name "Net-(IC1-RB5{slash}KBI1{slash}PGM)") (class "Default")
      (node (ref "IC1") (pin "26") (pinfunction "RB5/KBI1/PGM_26") (pintype "bidirectional"))
      (node (ref "IC4") (pin "5") (pinfunction "~{LDAC}_5") (pintype "input"))
    )
    (net (code "38") (name "Net-(IC1-RB6{slash}KBI2{slash}PGC)") (class "Default")
      (node (ref "IC1") (pin "27") (pinfunction "RB6/KBI2/PGC_27") (pintype "bidirectional"))
      (node (ref "R12") (pin "2") (pinfunction "2_2") (pintype "passive"))
    )
    (net (code "39") (name "Net-(IC1-RC0{slash}TIOSO{slash}T13CKI)") (class "Default")
      (node (ref "IC1") (pin "11") (pinfunction "RC0/TIOSO/T13CKI_11") (pintype "bidirectional"))
      (node (ref "IC2") (pin "5") (pinfunction "~{LDAC}_5") (pintype "input"))
    )
    (net (code "40") (name "Net-(IC1-RC1{slash}T1OSI{slash}ICCP2{slash}~{UOE})") (class "Default")
      (node (ref "IC1") (pin "12") (pinfunction "RC1/T1OSI/ICCP2/~{UOE}_12") (pintype "bidirectional"))
      (node (ref "IC2") (pin "2") (pinfunction "~{CS}_2") (pintype "input"))
    )
    (net (code "41") (name "Net-(IC1-RC2{slash}CCP1{slash}P1A)") (class "Default")
      (node (ref "IC1") (pin "13") (pinfunction "RC2/CCP1/P1A_13") (pintype "bidirectional"))
      (node (ref "R4") (pin "2") (pinfunction "2_2") (pintype "passive"))
      (node (ref "R5") (pin "2") (pinfunction "2_2") (pintype "passive"))
    )
    (net (code "42") (name "Net-(IC1-RC4{slash}D-{slash}VM)") (class "Default")
      (node (ref "IC1") (pin "15") (pinfunction "RC4/D-/VM_15") (pintype "bidirectional"))
      (node (ref "USB") (pin "2") (pinfunction "2_2") (pintype "passive"))
    )
    (net (code "43") (name "Net-(IC1-RC5{slash}D+{slash}VP)") (class "Default")
      (node (ref "IC1") (pin "16") (pinfunction "RC5/D+/VP_16") (pintype "bidirectional"))
      (node (ref "USB") (pin "3") (pinfunction "3_3") (pintype "passive"))
    )
    (net (code "44") (name "Net-(IC1-RC6{slash}TX{slash}CK)") (class "Default")
      (node (ref "IC1") (pin "17") (pinfunction "RC6/TX/CK_17") (pintype "bidirectional"))
      (node (ref "IC3") (pin "5") (pinfunction "~{LDAC}_5") (pintype "input"))
    )
    (net (code "45") (name "Net-(IC1-RC7{slash}RX{slash}DT{slash}SDO)") (class "Default")
      (node (ref "IC1") (pin "18") (pinfunction "RC7/RX/DT/SDO_18") (pintype "bidirectional"))
      (node (ref "IC2") (pin "4") (pinfunction "SDI_4") (pintype "input"))
      (node (ref "IC3") (pin "4") (pinfunction "SDI_4") (pintype "input"))
      (node (ref "IC4") (pin "4") (pinfunction "SDI_4") (pintype "input"))
      (node (ref "IC5") (pin "4") (pinfunction "SDI_4") (pintype "input"))
    )
    (net (code "46") (name "Net-(IC1-VUSB)") (class "Default")
      (node (ref "C5") (pin "1") (pinfunction "1_1") (pintype "passive"))
      (node (ref "IC1") (pin "14") (pinfunction "VUSB_14") (pintype "bidirectional"))
    )
    (net (code "47") (name "Net-(IC1-~{MCLR}{slash}VPP{slash}RE3)") (class "Default")
      (node (ref "C2") (pin "1") (pinfunction "1_1") (pintype "passive"))
      (node (ref "IC1") (pin "1") (pinfunction "~{MCLR}/VPP/RE3_1") (pintype "input"))
      (node (ref "R3") (pin "1") (pinfunction "1_1") (pintype "passive"))
      (node (ref "RST") (pin "3") (pinfunction "3_3") (pintype "passive"))
    )
    (net (code "48") (name "Net-(IC6A-+IN)") (class "Default")
      (node (ref "IC6") (pin "3") (pinfunction "+IN_3") (pintype "input"))
      (node (ref "R23") (pin "1") (pinfunction "1_1") (pintype "passive"))
      (node (ref "R7") (pin "2") (pinfunction "2_2") (pintype "passive"))
    )
    (net (code "49") (name "Net-(IC6A--IN)") (class "Default")
      (node (ref "IC6") (pin "2") (pinfunction "-IN_2") (pintype "input"))
      (node (ref "R10") (pin "2") (pinfunction "2_2") (pintype "passive"))
      (node (ref "R11") (pin "1") (pinfunction "1_1") (pintype "passive"))
    )
    (net (code "50") (name "Net-(IC6A-OUT)") (class "Default")
      (node (ref "IC6") (pin "1") (pinfunction "OUT_1") (pintype "output"))
      (node (ref "R11") (pin "2") (pinfunction "2_2") (pintype "passive"))
      (node (ref "R44") (pin "1") (pinfunction "1_1") (pintype "passive"))
    )
    (net (code "51") (name "Net-(IC6B-+IN)") (class "Default")
      (node (ref "IC6") (pin "5") (pinfunction "+IN_5") (pintype "input"))
      (node (ref "R22") (pin "1") (pinfunction "1_1") (pintype "passive"))
      (node (ref "R8") (pin "2") (pinfunction "2_2") (pintype "passive"))
    )
    (net (code "52") (name "Net-(IC6B--IN)") (class "Default")
      (node (ref "IC6") (pin "6") (pinfunction "-IN_6") (pintype "input"))
      (node (ref "R13") (pin "1") (pinfunction "1_1") (pintype "passive"))
      (node (ref "R15") (pin "2") (pinfunction "2_2") (pintype "passive"))
    )
    (net (code "53") (name "Net-(IC6B-OUT)") (class "Default")
      (node (ref "IC6") (pin "7") (pinfunction "OUT_7") (pintype "output"))
      (node (ref "R13") (pin "2") (pinfunction "2_2") (pintype "passive"))
      (node (ref "R47") (pin "1") (pinfunction "1_1") (pintype "passive"))
    )
    (net (code "54") (name "Net-(IC6C-+IN)") (class "Default")
      (node (ref "IC6") (pin "10") (pinfunction "+IN_10") (pintype "input"))
      (node (ref "R24") (pin "2") (pinfunction "2_2") (pintype "passive"))
      (node (ref "R41") (pin "1") (pinfunction "1_1") (pintype "passive"))
    )
    (net (code "55") (name "Net-(IC6C--IN)") (class "Default")
      (node (ref "IC6") (pin "9") (pinfunction "-IN_9") (pintype "input"))
      (node (ref "R14") (pin "2") (pinfunction "2_2") (pintype "passive"))
      (node (ref "R28") (pin "1") (pinfunction "1_1") (pintype "passive"))
    )
    (net (code "56") (name "Net-(IC6C-OUT)") (class "Default")
      (node (ref "IC6") (pin "8") (pinfunction "OUT_8") (pintype "output"))
      (node (ref "R28") (pin "2") (pinfunction "2_2") (pintype "passive"))
      (node (ref "R35") (pin "1") (pinfunction "1_1") (pintype "passive"))
    )
    (net (code "57") (name "Net-(IC6D-+IN)") (class "Default")
      (node (ref "IC6") (pin "12") (pinfunction "+IN_12") (pintype "input"))
      (node (ref "R25") (pin "2") (pinfunction "2_2") (pintype "passive"))
      (node (ref "R40") (pin "1") (pinfunction "1_1") (pintype "passive"))
    )
    (net (code "58") (name "Net-(IC6D--IN)") (class "Default")
      (node (ref "IC6") (pin "13") (pinfunction "-IN_13") (pintype "input"))
      (node (ref "R27") (pin "1") (pinfunction "1_1") (pintype "passive"))
      (node (ref "R9") (pin "2") (pinfunction "2_2") (pintype "passive"))
    )
    (net (code "59") (name "Net-(IC6D-OUT)") (class "Default")
      (node (ref "IC6") (pin "14") (pinfunction "OUT_14") (pintype "output"))
      (node (ref "R27") (pin "2") (pinfunction "2_2") (pintype "passive"))
      (node (ref "R32") (pin "1") (pinfunction "1_1") (pintype "passive"))
    )
    (net (code "60") (name "Net-(IC7A-+IN)") (class "Default")
      (node (ref "IC7") (pin "3") (pinfunction "+IN_3") (pintype "input"))
      (node (ref "R42") (pin "2") (pinfunction "2_2") (pintype "passive"))
      (node (ref "R53") (pin "1") (pinfunction "1_1") (pintype "passive"))
    )
    (net (code "61") (name "Net-(IC7A--IN)") (class "Default")
      (node (ref "IC7") (pin "2") (pinfunction "-IN_2") (pintype "input"))
      (node (ref "R16") (pin "2") (pinfunction "2_2") (pintype "passive"))
      (node (ref "R18") (pin "1") (pinfunction "1_1") (pintype "passive"))
    )
    (net (code "62") (name "Net-(IC7A-OUT)") (class "Default")
      (node (ref "IC7") (pin "1") (pinfunction "OUT_1") (pintype "output"))
      (node (ref "R18") (pin "2") (pinfunction "2_2") (pintype "passive"))
      (node (ref "R48") (pin "1") (pinfunction "1_1") (pintype "passive"))
    )
    (net (code "63") (name "Net-(IC7B-+IN)") (class "Default")
      (node (ref "IC7") (pin "5") (pinfunction "+IN_5") (pintype "input"))
      (node (ref "R54") (pin "2") (pinfunction "2_2") (pintype "passive"))
      (node (ref "R57") (pin "1") (pinfunction "1_1") (pintype "passive"))
    )
    (net (code "64") (name "Net-(IC7B--IN)") (class "Default")
      (node (ref "IC7") (pin "6") (pinfunction "-IN_6") (pintype "input"))
      (node (ref "R19") (pin "1") (pinfunction "1_1") (pintype "passive"))
      (node (ref "R20") (pin "2") (pinfunction "2_2") (pintype "passive"))
    )
    (net (code "65") (name "Net-(IC7B-OUT)") (class "Default")
      (node (ref "IC7") (pin "7") (pinfunction "OUT_7") (pintype "output"))
      (node (ref "R19") (pin "2") (pinfunction "2_2") (pintype "passive"))
      (node (ref "R51") (pin "1") (pinfunction "1_1") (pintype "passive"))
    )
    (net (code "66") (name "Net-(IC7C-+IN)") (class "Default")
      (node (ref "IC7") (pin "10") (pinfunction "+IN_10") (pintype "input"))
      (node (ref "R55") (pin "2") (pinfunction "2_2") (pintype "passive"))
      (node (ref "R56") (pin "1") (pinfunction "1_1") (pintype "passive"))
    )
    (net (code "67") (name "Net-(IC7C--IN)") (class "Default")
      (node (ref "IC7") (pin "9") (pinfunction "-IN_9") (pintype "input"))
      (node (ref "R21") (pin "2") (pinfunction "2_2") (pintype "passive"))
      (node (ref "R30") (pin "1") (pinfunction "1_1") (pintype "passive"))
    )
    (net (code "68") (name "Net-(IC7C-OUT)") (class "Default")
      (node (ref "IC7") (pin "8") (pinfunction "OUT_8") (pintype "output"))
      (node (ref "R30") (pin "2") (pinfunction "2_2") (pintype "passive"))
      (node (ref "R39") (pin "1") (pinfunction "1_1") (pintype "passive"))
    )
    (net (code "69") (name "Net-(IC7D-+IN)") (class "Default")
      (node (ref "IC7") (pin "12") (pinfunction "+IN_12") (pintype "input"))
      (node (ref "R43") (pin "2") (pinfunction "2_2") (pintype "passive"))
      (node (ref "R52") (pin "1") (pinfunction "1_1") (pintype "passive"))
    )
    (net (code "70") (name "Net-(IC7D--IN)") (class "Default")
      (node (ref "IC7") (pin "13") (pinfunction "-IN_13") (pintype "input"))
      (node (ref "R17") (pin "2") (pinfunction "2_2") (pintype "passive"))
      (node (ref "R29") (pin "1") (pinfunction "1_1") (pintype "passive"))
    )
    (net (code "71") (name "Net-(IC7D-OUT)") (class "Default")
      (node (ref "IC7") (pin "14") (pinfunction "OUT_14") (pintype "output"))
      (node (ref "R29") (pin "2") (pinfunction "2_2") (pintype "passive"))
      (node (ref "R36") (pin "1") (pinfunction "1_1") (pintype "passive"))
    )
    (net (code "72") (name "Net-(IC8A-+IN)") (class "Default")
      (node (ref "C14") (pin "1") (pinfunction "1_1") (pintype "passive"))
      (node (ref "IC8") (pin "3") (pinfunction "+IN_3") (pintype "input"))
      (node (ref "R33") (pin "2") (pinfunction "2_2") (pintype "passive"))
    )
    (net (code "73") (name "Net-(IC8A--IN)") (class "Default")
      (node (ref "C13") (pin "2") (pinfunction "2_2") (pintype "passive"))
      (node (ref "IC8") (pin "1") (pinfunction "OUT_1") (pintype "output"))
      (node (ref "IC8") (pin "2") (pinfunction "-IN_2") (pintype "input"))
      (node (ref "R72") (pin "1") (pinfunction "1_1") (pintype "passive"))
    )
    (net (code "74") (name "Net-(IC8B-+IN)") (class "Default")
      (node (ref "C15") (pin "1") (pinfunction "1_1") (pintype "passive"))
      (node (ref "IC8") (pin "5") (pinfunction "+IN_5") (pintype "input"))
      (node (ref "R34") (pin "2") (pinfunction "2_2") (pintype "passive"))
    )
    (net (code "75") (name "Net-(IC8B--IN)") (class "Default")
      (node (ref "C16") (pin "2") (pinfunction "2_2") (pintype "passive"))
      (node (ref "IC8") (pin "6") (pinfunction "-IN_6") (pintype "input"))
      (node (ref "IC8") (pin "7") (pinfunction "OUT_7") (pintype "output"))
      (node (ref "R74") (pin "1") (pinfunction "1_1") (pintype "passive"))
    )
    (net (code "76") (name "Net-(IC8C-+IN)") (class "Default")
      (node (ref "C25") (pin "1") (pinfunction "1_1") (pintype "passive"))
      (node (ref "IC8") (pin "10") (pinfunction "+IN_10") (pintype "input"))
      (node (ref "R46") (pin "2") (pinfunction "2_2") (pintype "passive"))
    )
    (net (code "77") (name "Net-(IC8C--IN)") (class "Default")
      (node (ref "C26") (pin "2") (pinfunction "2_2") (pintype "passive"))
      (node (ref "IC8") (pin "8") (pinfunction "OUT_8") (pintype "output"))
      (node (ref "IC8") (pin "9") (pinfunction "-IN_9") (pintype "input"))
      (node (ref "R61") (pin "1") (pinfunction "1_1") (pintype "passive"))
    )
    (net (code "78") (name "Net-(IC8D-+IN)") (class "Default")
      (node (ref "C24") (pin "1") (pinfunction "1_1") (pintype "passive"))
      (node (ref "IC8") (pin "12") (pinfunction "+IN_12") (pintype "input"))
      (node (ref "R45") (pin "2") (pinfunction "2_2") (pintype "passive"))
    )
    (net (code "79") (name "Net-(IC8D--IN)") (class "Default")
      (node (ref "C23") (pin "2") (pinfunction "2_2") (pintype "passive"))
      (node (ref "IC8") (pin "13") (pinfunction "-IN_13") (pintype "input"))
      (node (ref "IC8") (pin "14") (pinfunction "OUT_14") (pintype "output"))
      (node (ref "R60") (pin "1") (pinfunction "1_1") (pintype "passive"))
    )
    (net (code "80") (name "Net-(IC9A-+IN)") (class "Default")
      (node (ref "C19") (pin "1") (pinfunction "1_1") (pintype "passive"))
      (node (ref "IC9") (pin "3") (pinfunction "+IN_3") (pintype "input"))
      (node (ref "R37") (pin "2") (pinfunction "2_2") (pintype "passive"))
    )
    (net (code "81") (name "Net-(IC9A--IN)") (class "Default")
      (node (ref "C18") (pin "2") (pinfunction "2_2") (pintype "passive"))
      (node (ref "IC9") (pin "1") (pinfunction "OUT_1") (pintype "output"))
      (node (ref "IC9") (pin "2") (pinfunction "-IN_2") (pintype "input"))
      (node (ref "R78") (pin "1") (pinfunction "1_1") (pintype "passive"))
    )
    (net (code "82") (name "Net-(IC9B-+IN)") (class "Default")
      (node (ref "C20") (pin "1") (pinfunction "1_1") (pintype "passive"))
      (node (ref "IC9") (pin "5") (pinfunction "+IN_5") (pintype "input"))
      (node (ref "R38") (pin "2") (pinfunction "2_2") (pintype "passive"))
    )
    (net (code "83") (name "Net-(IC9B--IN)") (class "Default")
      (node (ref "C21") (pin "2") (pinfunction "2_2") (pintype "passive"))
      (node (ref "IC9") (pin "6") (pinfunction "-IN_6") (pintype "input"))
      (node (ref "IC9") (pin "7") (pinfunction "OUT_7") (pintype "output"))
      (node (ref "R80") (pin "1") (pinfunction "1_1") (pintype "passive"))
    )
    (net (code "84") (name "Net-(IC9C-+IN)") (class "Default")
      (node (ref "C30") (pin "1") (pinfunction "1_1") (pintype "passive"))
      (node (ref "IC9") (pin "10") (pinfunction "+IN_10") (pintype "input"))
      (node (ref "R50") (pin "2") (pinfunction "2_2") (pintype "passive"))
    )
    (net (code "85") (name "Net-(IC9C--IN)") (class "Default")
      (node (ref "C31") (pin "2") (pinfunction "2_2") (pintype "passive"))
      (node (ref "IC9") (pin "8") (pinfunction "OUT_8") (pintype "output"))
      (node (ref "IC9") (pin "9") (pinfunction "-IN_9") (pintype "input"))
      (node (ref "R67") (pin "1") (pinfunction "1_1") (pintype "passive"))
    )
    (net (code "86") (name "Net-(IC9D-+IN)") (class "Default")
      (node (ref "C29") (pin "1") (pinfunction "1_1") (pintype "passive"))
      (node (ref "IC9") (pin "12") (pinfunction "+IN_12") (pintype "input"))
      (node (ref "R49") (pin "2") (pinfunction "2_2") (pintype "passive"))
    )
    (net (code "87") (name "Net-(IC9D--IN)") (class "Default")
      (node (ref "C28") (pin "2") (pinfunction "2_2") (pintype "passive"))
      (node (ref "IC9") (pin "13") (pinfunction "-IN_13") (pintype "input"))
      (node (ref "IC9") (pin "14") (pinfunction "OUT_14") (pintype "output"))
      (node (ref "R66") (pin "1") (pinfunction "1_1") (pintype "passive"))
    )
    (net (code "88") (name "Net-(IC10A-+IN)") (class "Default")
      (node (ref "IC10") (pin "3") (pinfunction "+IN_3") (pintype "input"))
      (node (ref "R60") (pin "2") (pinfunction "2_2") (pintype "passive"))
    )
    (net (code "89") (name "Net-(IC10A--IN)") (class "Default")
      (node (ref "IC10") (pin "2") (pinfunction "-IN_2") (pintype "input"))
      (node (ref "R58") (pin "2") (pinfunction "2_2") (pintype "passive"))
      (node (ref "R70") (pin "1") (pinfunction "1_1") (pintype "passive"))
    )
    (net (code "90") (name "Net-(IC10A-OUT)") (class "Default")
      (node (ref "IC10") (pin "1") (pinfunction "OUT_1") (pintype "output"))
      (node (ref "R82") (pin "2") (pinfunction "S_2") (pintype "passive"))
      (node (ref "R82") (pin "3") (pinfunction "E_3") (pintype "passive"))
      (node (ref "SADI") (pin "2") (pinfunction "2_2") (pintype "passive"))
    )
    (net (code "91") (name "Net-(IC10B-+IN)") (class "Default")
      (node (ref "IC10") (pin "5") (pinfunction "+IN_5") (pintype "input"))
      (node (ref "R61") (pin "2") (pinfunction "2_2") (pintype "passive"))
    )
    (net (code "92") (name "Net-(IC10B--IN)") (class "Default")
      (node (ref "IC10") (pin "6") (pinfunction "-IN_6") (pintype "input"))
      (node (ref "R63") (pin "2") (pinfunction "2_2") (pintype "passive"))
      (node (ref "R75") (pin "1") (pinfunction "1_1") (pintype "passive"))
    )
    (net (code "93") (name "Net-(IC10B-OUT)") (class "Default")
      (node (ref "IC10") (pin "7") (pinfunction "OUT_7") (pintype "output"))
      (node (ref "R85") (pin "2") (pinfunction "S_2") (pintype "passive"))
      (node (ref "R85") (pin "3") (pinfunction "E_3") (pintype "passive"))
      (node (ref "SADI") (pin "6") (pinfunction "6_6") (pintype "passive"))
    )
    (net (code "94") (name "Net-(IC10C-+IN)") (class "Default")
      (node (ref "IC10") (pin "10") (pinfunction "+IN_10") (pintype "input"))
      (node (ref "R74") (pin "2") (pinfunction "2_2") (pintype "passive"))
    )
    (net (code "95") (name "Net-(IC10C--IN)") (class "Default")
      (node (ref "IC10") (pin "9") (pinfunction "-IN_9") (pintype "input"))
      (node (ref "R62") (pin "2") (pinfunction "2_2") (pintype "passive"))
      (node (ref "R73") (pin "1") (pinfunction "1_1") (pintype "passive"))
    )
    (net (code "96") (name "Net-(IC10C-OUT)") (class "Default")
      (node (ref "IC10") (pin "8") (pinfunction "OUT_8") (pintype "output"))
      (node (ref "R84") (pin "2") (pinfunction "S_2") (pintype "passive"))
      (node (ref "R84") (pin "3") (pinfunction "E_3") (pintype "passive"))
      (node (ref "SADI") (pin "4") (pinfunction "4_4") (pintype "passive"))
    )
    (net (code "97") (name "Net-(IC10D-+IN)") (class "Default")
      (node (ref "IC10") (pin "12") (pinfunction "+IN_12") (pintype "input"))
      (node (ref "R72") (pin "2") (pinfunction "2_2") (pintype "passive"))
    )
    (net (code "98") (name "Net-(IC10D--IN)") (class "Default")
      (node (ref "IC10") (pin "13") (pinfunction "-IN_13") (pintype "input"))
      (node (ref "R59") (pin "2") (pinfunction "2_2") (pintype "passive"))
      (node (ref "R71") (pin "1") (pinfunction "1_1") (pintype "passive"))
    )
    (net (code "99") (name "Net-(IC10D-OUT)") (class "Default")
      (node (ref "IC10") (pin "14") (pinfunction "OUT_14") (pintype "output"))
      (node (ref "R83") (pin "2") (pinfunction "S_2") (pintype "passive"))
      (node (ref "R83") (pin "3") (pinfunction "E_3") (pintype "passive"))
      (node (ref "SADI") (pin "10") (pinfunction "10_10") (pintype "passive"))
    )
    (net (code "100") (name "Net-(IC11A-+IN)") (class "Default")
      (node (ref "IC11") (pin "3") (pinfunction "+IN_3") (pintype "input"))
      (node (ref "R66") (pin "2") (pinfunction "2_2") (pintype "passive"))
    )
    (net (code "101") (name "Net-(IC11A--IN)") (class "Default")
      (node (ref "IC11") (pin "2") (pinfunction "-IN_2") (pintype "input"))
      (node (ref "R64") (pin "2") (pinfunction "2_2") (pintype "passive"))
      (node (ref "R76") (pin "1") (pinfunction "1_1") (pintype "passive"))
    )
    (net (code "102") (name "Net-(IC11A-OUT)") (class "Default")
      (node (ref "DVC2.3") (pin "4") (pinfunction "4_4") (pintype "passive"))
      (node (ref "IC11") (pin "1") (pinfunction "OUT_1") (pintype "output"))
      (node (ref "R86") (pin "2") (pinfunction "S_2") (pintype "passive"))
      (node (ref "R86") (pin "3") (pinfunction "E_3") (pintype "passive"))
    )
    (net (code "103") (name "Net-(IC11B-+IN)") (class "Default")
      (node (ref "IC11") (pin "5") (pinfunction "+IN_5") (pintype "input"))
      (node (ref "R67") (pin "2") (pinfunction "2_2") (pintype "passive"))
    )
    (net (code "104") (name "Net-(IC11B--IN)") (class "Default")
      (node (ref "IC11") (pin "6") (pinfunction "-IN_6") (pintype "input"))
      (node (ref "R69") (pin "2") (pinfunction "2_2") (pintype "passive"))
      (node (ref "R81") (pin "1") (pinfunction "1_1") (pintype "passive"))
    )
    (net (code "105") (name "Net-(IC11B-OUT)") (class "Default")
      (node (ref "DVC2.3") (pin "8") (pinfunction "8_8") (pintype "passive"))
      (node (ref "IC11") (pin "7") (pinfunction "OUT_7") (pintype "output"))
      (node (ref "R89") (pin "2") (pinfunction "S_2") (pintype "passive"))
      (node (ref "R89") (pin "3") (pinfunction "E_3") (pintype "passive"))
    )
    (net (code "106") (name "Net-(IC11C-+IN)") (class "Default")
      (node (ref "IC11") (pin "10") (pinfunction "+IN_10") (pintype "input"))
      (node (ref "R80") (pin "2") (pinfunction "2_2") (pintype "passive"))
    )
    (net (code "107") (name "Net-(IC11C--IN)") (class "Default")
      (node (ref "IC11") (pin "9") (pinfunction "-IN_9") (pintype "input"))
      (node (ref "R68") (pin "2") (pinfunction "2_2") (pintype "passive"))
      (node (ref "R79") (pin "1") (pinfunction "1_1") (pintype "passive"))
    )
    (net (code "108") (name "Net-(IC11C-OUT)") (class "Default")
      (node (ref "DVC2.3") (pin "6") (pinfunction "6_6") (pintype "passive"))
      (node (ref "IC11") (pin "8") (pinfunction "OUT_8") (pintype "output"))
      (node (ref "R88") (pin "2") (pinfunction "S_2") (pintype "passive"))
      (node (ref "R88") (pin "3") (pinfunction "E_3") (pintype "passive"))
    )
    (net (code "109") (name "Net-(IC11D-+IN)") (class "Default")
      (node (ref "IC11") (pin "12") (pinfunction "+IN_12") (pintype "input"))
      (node (ref "R78") (pin "2") (pinfunction "2_2") (pintype "passive"))
    )
    (net (code "110") (name "Net-(IC11D--IN)") (class "Default")
      (node (ref "IC11") (pin "13") (pinfunction "-IN_13") (pintype "input"))
      (node (ref "R65") (pin "2") (pinfunction "2_2") (pintype "passive"))
      (node (ref "R77") (pin "1") (pinfunction "1_1") (pintype "passive"))
    )
    (net (code "111") (name "Net-(IC11D-OUT)") (class "Default")
      (node (ref "DVC2.3") (pin "2") (pinfunction "2_2") (pintype "passive"))
      (node (ref "IC11") (pin "14") (pinfunction "OUT_14") (pintype "output"))
      (node (ref "R87") (pin "2") (pinfunction "S_2") (pintype "passive"))
      (node (ref "R87") (pin "3") (pinfunction "E_3") (pintype "passive"))
    )
    (net (code "112") (name "Net-(IC12-+IN)") (class "Default")
      (node (ref "C34") (pin "1") (pinfunction "1_1") (pintype "passive"))
      (node (ref "IC12") (pin "3") (pinfunction "+IN_3") (pintype "input"))
      (node (ref "R90") (pin "2") (pinfunction "S_2") (pintype "passive"))
    )
    (net (code "113") (name "Net-(R4-Pad1)") (class "Default")
      (node (ref "R4") (pin "1") (pinfunction "1_1") (pintype "passive"))
      (node (ref "USB") (pin "1") (pinfunction "1_1") (pintype "passive"))
    )
    (net (code "114") (name "Net-(R26-Pad1)") (class "Default")
      (node (ref "R26") (pin "1") (pinfunction "1_1") (pintype "passive"))
      (node (ref "R31") (pin "1") (pinfunction "1_1") (pintype "passive"))
      (node (ref "T2") (pin "C") (pinfunction "C_C") (pintype "passive"))
    )
    (net (code "115") (name "Net-(R31-Pad2)") (class "Default")
      (node (ref "R31") (pin "2") (pinfunction "2_2") (pintype "passive"))
      (node (ref "T1") (pin "B") (pinfunction "B_B") (pintype "passive"))
    )
    (net (code "116") (name "Net-(R82-A)") (class "Default")
      (node (ref "R70") (pin "2") (pinfunction "2_2") (pintype "passive"))
      (node (ref "R82") (pin "1") (pinfunction "A_1") (pintype "passive"))
    )
    (net (code "117") (name "Net-(R83-A)") (class "Default")
      (node (ref "R71") (pin "2") (pinfunction "2_2") (pintype "passive"))
      (node (ref "R83") (pin "1") (pinfunction "A_1") (pintype "passive"))
    )
    (net (code "118") (name "Net-(R84-A)") (class "Default")
      (node (ref "R73") (pin "2") (pinfunction "2_2") (pintype "passive"))
      (node (ref "R84") (pin "1") (pinfunction "A_1") (pintype "passive"))
    )
    (net (code "119") (name "Net-(R85-A)") (class "Default")
      (node (ref "R75") (pin "2") (pinfunction "2_2") (pintype "passive"))
      (node (ref "R85") (pin "1") (pinfunction "A_1") (pintype "passive"))
    )
    (net (code "120") (name "Net-(R86-A)") (class "Default")
      (node (ref "R76") (pin "2") (pinfunction "2_2") (pintype "passive"))
      (node (ref "R86") (pin "1") (pinfunction "A_1") (pintype "passive"))
    )
    (net (code "121") (name "Net-(R87-A)") (class "Default")
      (node (ref "R77") (pin "2") (pinfunction "2_2") (pintype "passive"))
      (node (ref "R87") (pin "1") (pinfunction "A_1") (pintype "passive"))
    )
    (net (code "122") (name "Net-(R88-A)") (class "Default")
      (node (ref "R79") (pin "2") (pinfunction "2_2") (pintype "passive"))
      (node (ref "R88") (pin "1") (pinfunction "A_1") (pintype "passive"))
    )
    (net (code "123") (name "Net-(R89-A)") (class "Default")
      (node (ref "R81") (pin "2") (pinfunction "2_2") (pintype "passive"))
      (node (ref "R89") (pin "1") (pinfunction "A_1") (pintype "passive"))
    )
    (net (code "124") (name "Net-(R90-E)") (class "Default")
      (node (ref "R90") (pin "3") (pinfunction "E_3") (pintype "passive"))
      (node (ref "R91") (pin "2") (pinfunction "2_2") (pintype "passive"))
    )
    (net (code "125") (name "Net-(SADI-Pad12)") (class "Default")
      (node (ref "SADI") (pin "12") (pinfunction "12_12") (pintype "passive"))
      (node (ref "T1") (pin "E") (pinfunction "E_E") (pintype "passive"))
    )
    (net (code "126") (name "OFF_FLG") (class "Default")
      (node (ref "R12") (pin "1") (pinfunction "1_1") (pintype "passive"))
      (node (ref "T2") (pin "B") (pinfunction "B_B") (pintype "passive"))
    )
    (net (code "127") (name "OUT") (class "Default")
      (node (ref "DVC2.3") (pin "10") (pinfunction "10_10") (pintype "passive"))
      (node (ref "IC1") (pin "28") (pinfunction "RB7/BKI3/PGD_28") (pintype "bidirectional"))
    )
    (net (code "128") (name "SHIFT") (class "Default")
      (node (ref "IC12") (pin "2") (pinfunction "-IN_2") (pintype "input"))
      (node (ref "IC12") (pin "6") (pinfunction "OUT_6") (pintype "output"))
      (node (ref "R10") (pin "1") (pinfunction "1_1") (pintype "passive"))
      (node (ref "R14") (pin "1") (pinfunction "1_1") (pintype "passive"))
      (node (ref "R15") (pin "1") (pinfunction "1_1") (pintype "passive"))
      (node (ref "R16") (pin "1") (pinfunction "1_1") (pintype "passive"))
      (node (ref "R17") (pin "1") (pinfunction "1_1") (pintype "passive"))
      (node (ref "R20") (pin "1") (pinfunction "1_1") (pintype "passive"))
      (node (ref "R21") (pin "1") (pinfunction "1_1") (pintype "passive"))
      (node (ref "R9") (pin "1") (pinfunction "1_1") (pintype "passive"))
      (node (ref "TP1") (pin "TP") (pinfunction "TP_TP") (pintype "input"))
    )
    (net (code "129") (name "unconnected-(DC/DC-ON{slash}OFF-Pad3)") (class "Default")
      (node (ref "DC/DC") (pin "3") (pinfunction "ON/OFF_3") (pintype "passive"))
    )
    (net (code "130") (name "unconnected-(IC1-RB0{slash}AN12{slash}INT0{slash}LFT0{slash}SDI{slash}SDA-Pad21)") (class "Default")
      (node (ref "IC1") (pin "21") (pinfunction "RB0/AN12/INT0/LFT0/SDI/SDA_21") (pintype "bidirectional"))
    )
    (net (code "131") (name "unconnected-(IC12-ON1-Pad1)") (class "Default")
      (node (ref "IC12") (pin "1") (pinfunction "ON1_1") (pintype "passive"))
    )
    (net (code "132") (name "unconnected-(IC12-ON2-Pad5)") (class "Default")
      (node (ref "IC12") (pin "5") (pinfunction "ON2_5") (pintype "passive"))
    )
    (net (code "133") (name "unconnected-(IC12-OPT-Pad8)") (class "Default")
      (node (ref "IC12") (pin "8") (pinfunction "OPT_8") (pintype "passive"))
    )
  )
)
